# fc-comms-2.net
KiCad netlist of a schematic drawn in EAGLE
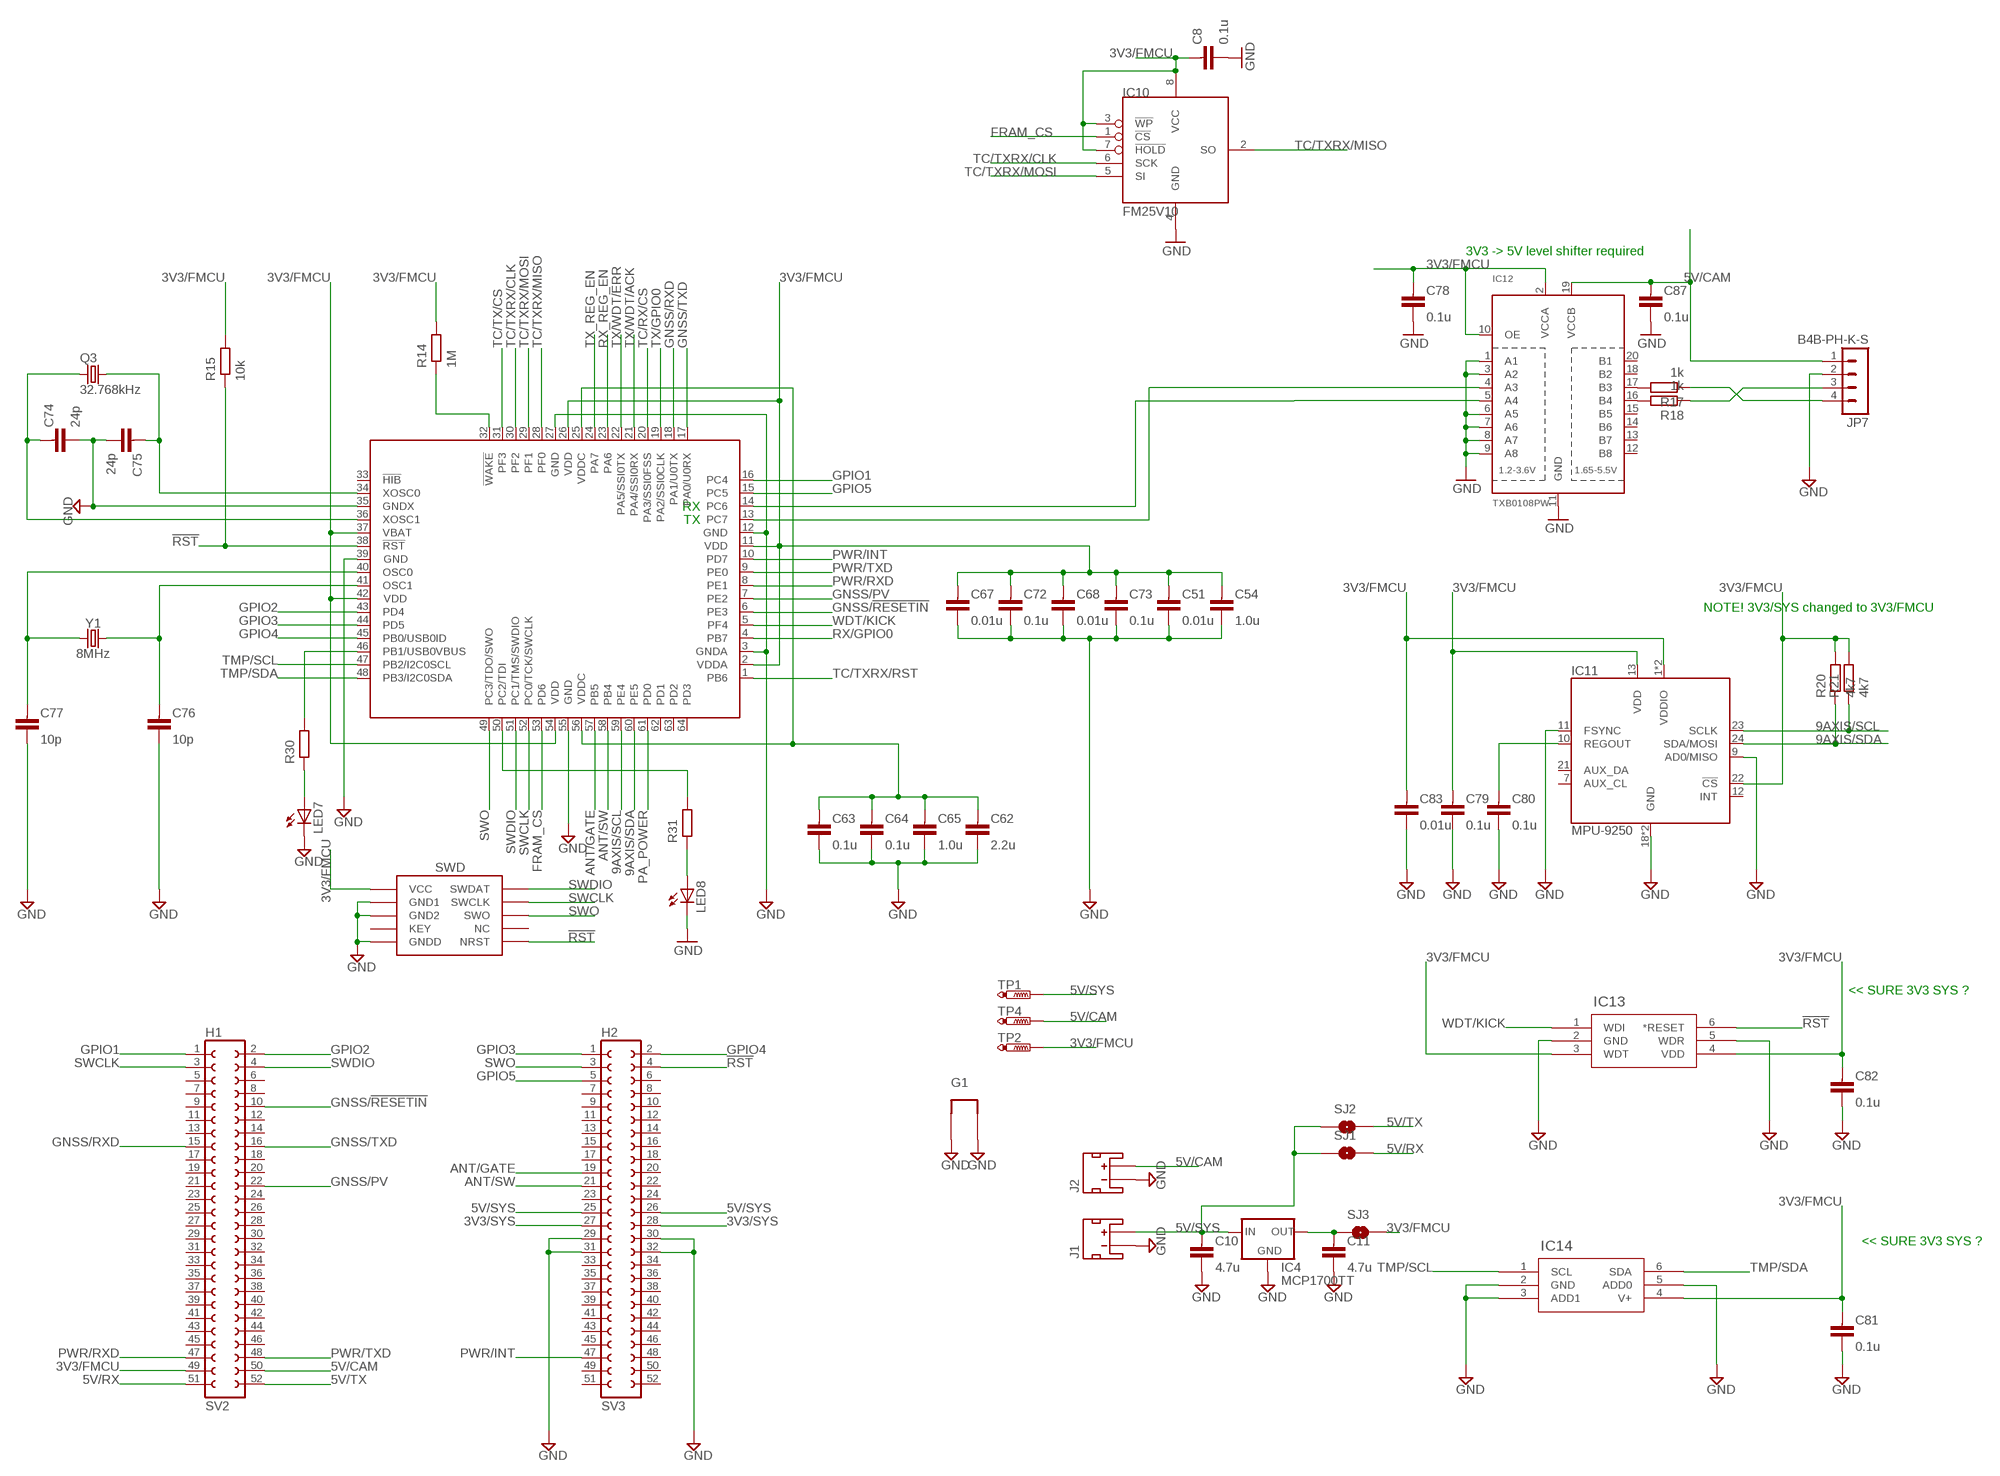
[diagram p0: schematic, sheet 1]
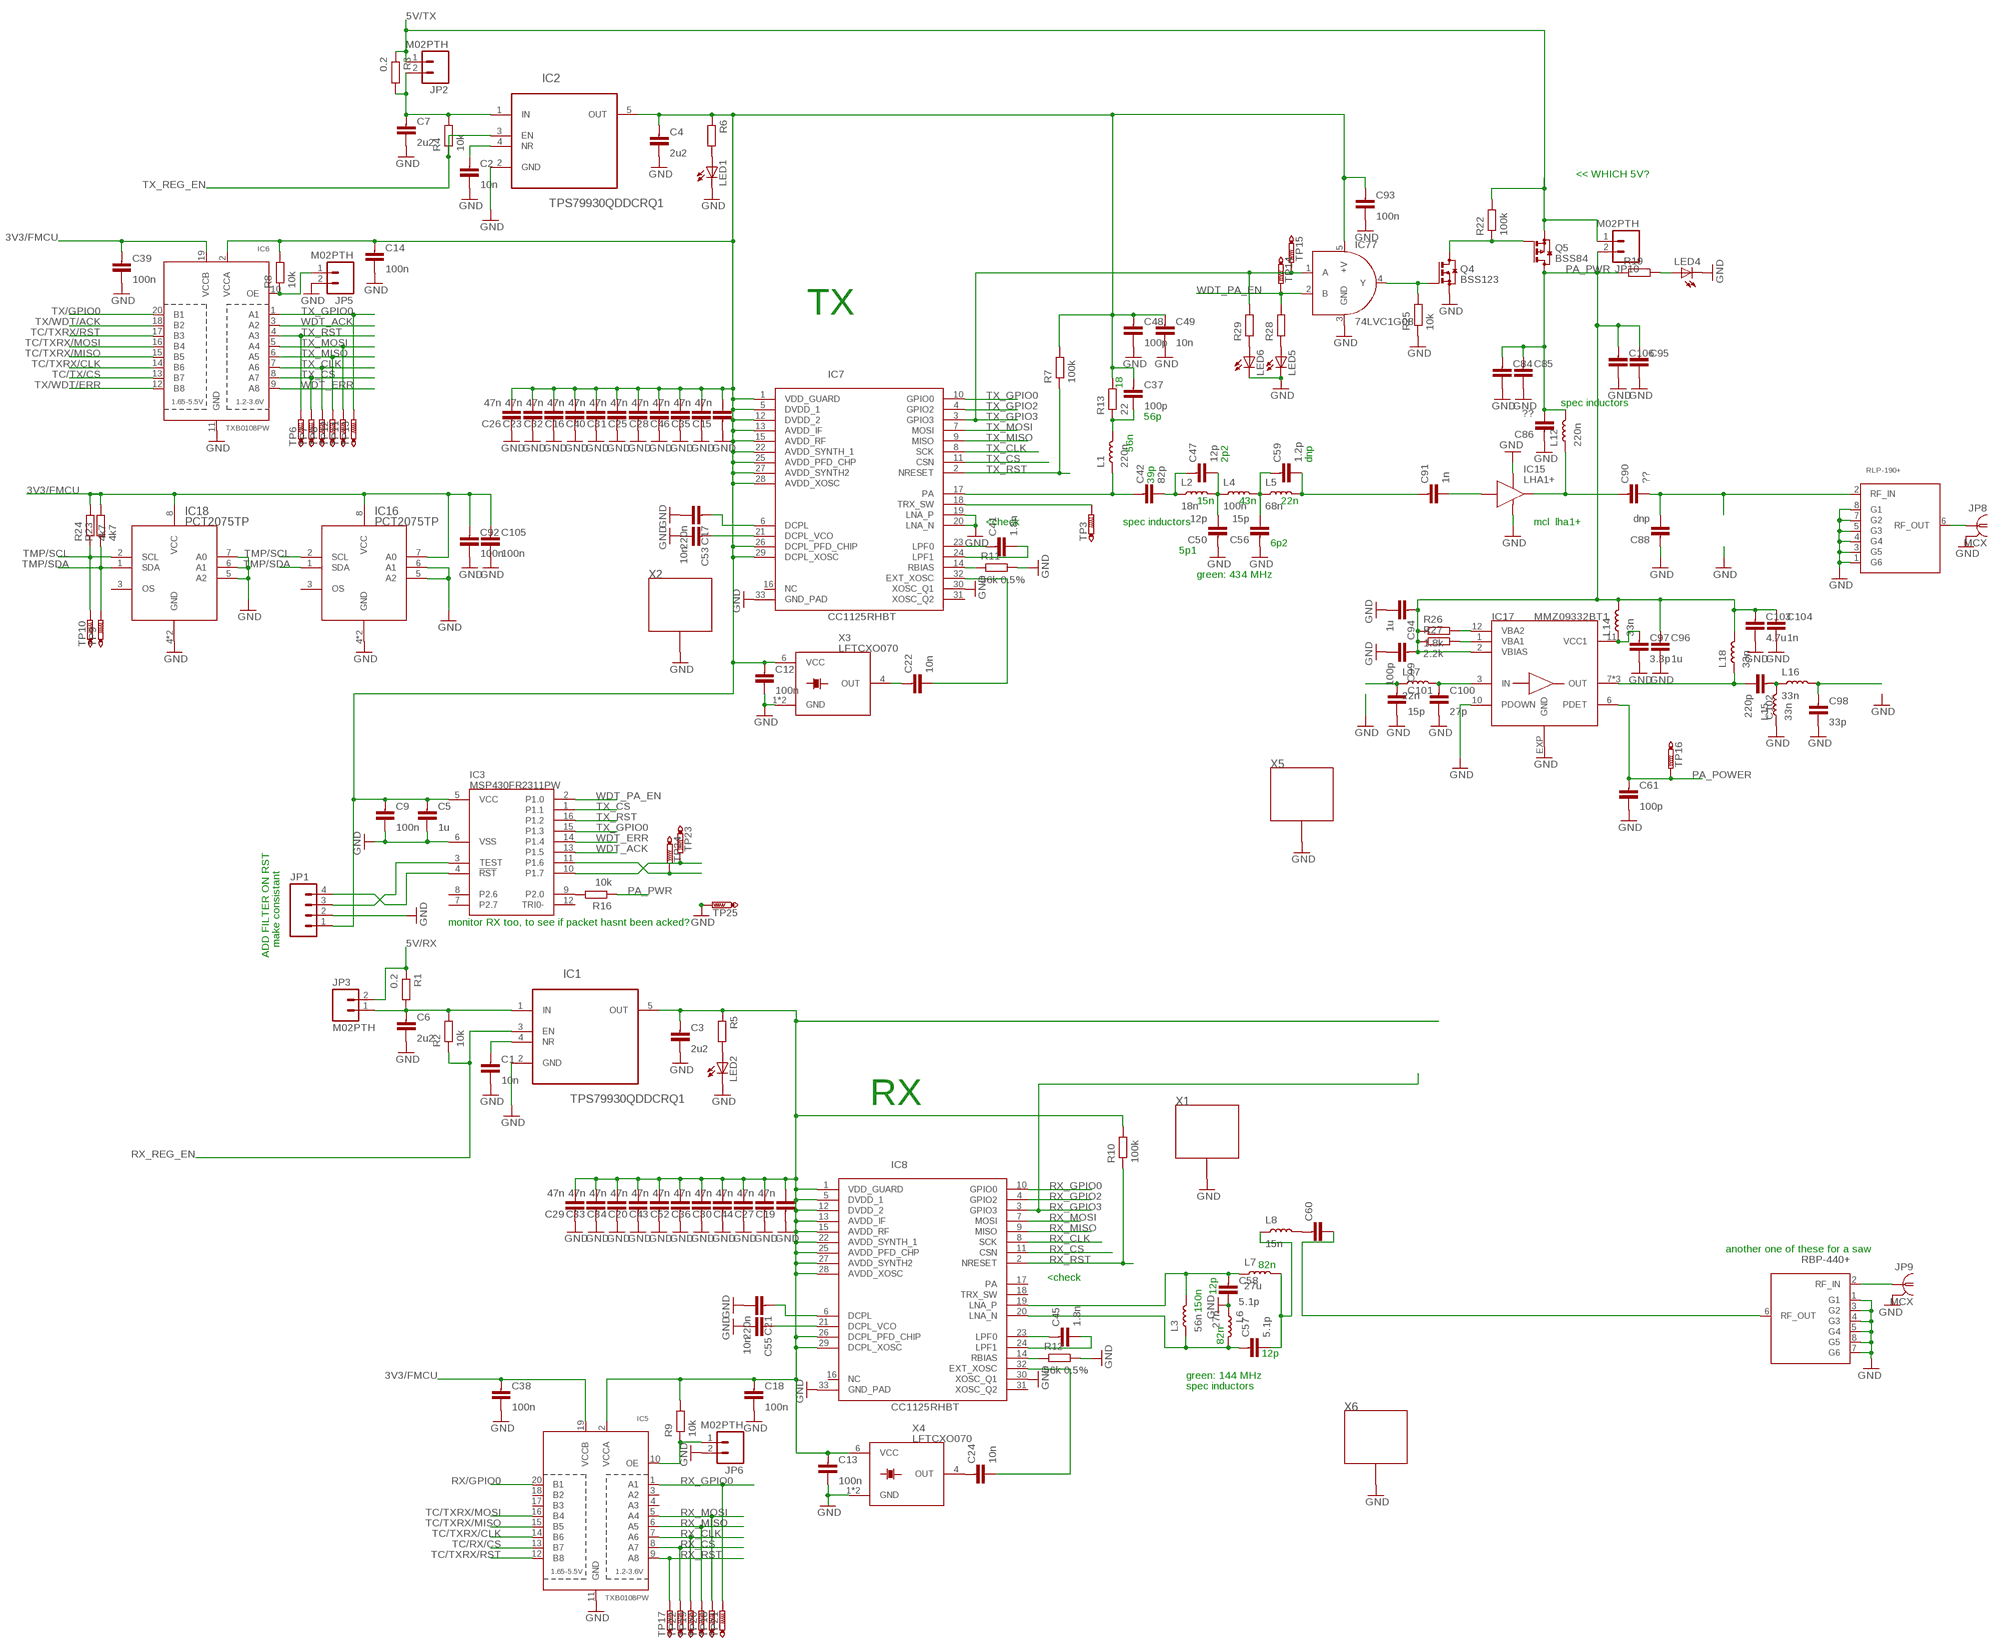
[diagram p1: schematic, sheet 2]

(export (version "E")
  (design (tool "Eeschema 10.0.6"))
  (components
    (comp (ref "C8")
      (value "0.1u")
      (footprint "eagle-import:C0603-N")
      (libsource (lib "eagle-import") (part "CAPACITOR0603-N"))
    )
    (comp (ref "C10")
      (value "4.7u")
      (footprint "eagle-import:C0603-N")
      (libsource (lib "eagle-import") (part "CAPACITOR0603-N"))
    )
    (comp (ref "C11")
      (value "4.7u")
      (footprint "eagle-import:C0603-N")
      (libsource (lib "eagle-import") (part "CAPACITOR0603-N"))
    )
    (comp (ref "C51")
      (value "0.01u")
      (footprint "eagle-import:C0603-N")
      (libsource (lib "eagle-import") (part "CAPACITOR0603-N"))
    )
    (comp (ref "C54")
      (value "1.0u")
      (footprint "eagle-import:C0603-N")
      (libsource (lib "eagle-import") (part "CAPACITOR0603-N"))
    )
    (comp (ref "C62")
      (value "2.2u")
      (footprint "eagle-import:C0603-N")
      (libsource (lib "eagle-import") (part "CAPACITOR0603-N"))
    )
    (comp (ref "C63")
      (value "0.1u")
      (footprint "eagle-import:C0603-N")
      (libsource (lib "eagle-import") (part "CAPACITOR0603-N"))
    )
    (comp (ref "C64")
      (value "0.1u")
      (footprint "eagle-import:C0603-N")
      (libsource (lib "eagle-import") (part "CAPACITOR0603-N"))
    )
    (comp (ref "C65")
      (value "1.0u")
      (footprint "eagle-import:C0603-N")
      (libsource (lib "eagle-import") (part "CAPACITOR0603-N"))
    )
    (comp (ref "C67")
      (value "0.01u")
      (footprint "eagle-import:C0603-N")
      (libsource (lib "eagle-import") (part "CAPACITOR0603-N"))
    )
    (comp (ref "C68")
      (value "0.01u")
      (footprint "eagle-import:C0603-N")
      (libsource (lib "eagle-import") (part "CAPACITOR0603-N"))
    )
    (comp (ref "C72")
      (value "0.1u")
      (footprint "eagle-import:C0603-N")
      (libsource (lib "eagle-import") (part "CAPACITOR0603-N"))
    )
    (comp (ref "C73")
      (value "0.1u")
      (footprint "eagle-import:C0603-N")
      (libsource (lib "eagle-import") (part "CAPACITOR0603-N"))
    )
    (comp (ref "C74")
      (value "24p")
      (footprint "eagle-import:C0603-N")
      (libsource (lib "eagle-import") (part "CAPACITOR0603-N"))
    )
    (comp (ref "C75")
      (value "24p")
      (footprint "eagle-import:C0603-N")
      (libsource (lib "eagle-import") (part "CAPACITOR0603-N"))
    )
    (comp (ref "C76")
      (value "10p")
      (footprint "eagle-import:C0603-N")
      (libsource (lib "eagle-import") (part "CAPACITOR0603-N"))
    )
    (comp (ref "C77")
      (value "10p")
      (footprint "eagle-import:C0603-N")
      (libsource (lib "eagle-import") (part "CAPACITOR0603-N"))
    )
    (comp (ref "C78")
      (value "0.1u")
      (footprint "eagle-import:C0603-N")
      (libsource (lib "eagle-import") (part "CAPACITOR0603-N"))
    )
    (comp (ref "C79")
      (value "0.1u")
      (footprint "eagle-import:C0603-N")
      (libsource (lib "eagle-import") (part "CAPACITOR0603-N"))
    )
    (comp (ref "C80")
      (value "0.1u")
      (footprint "eagle-import:C0603-N")
      (libsource (lib "eagle-import") (part "CAPACITOR0603-N"))
    )
    (comp (ref "C81")
      (value "0.1u")
      (footprint "eagle-import:C0603-N")
      (libsource (lib "eagle-import") (part "CAPACITOR0603-N"))
    )
    (comp (ref "C82")
      (value "0.1u")
      (footprint "eagle-import:C0603-N")
      (libsource (lib "eagle-import") (part "CAPACITOR0603-N"))
    )
    (comp (ref "C83")
      (value "0.01u")
      (footprint "eagle-import:C0603-N")
      (libsource (lib "eagle-import") (part "CAPACITOR0603-N"))
    )
    (comp (ref "C87")
      (value "0.1u")
      (footprint "eagle-import:C0603-N")
      (libsource (lib "eagle-import") (part "CAPACITOR0603-N"))
    )
    (comp (ref "G1")
      (value "GND-LOOPL")
      (footprint "eagle-import:GND-LOOP-0.4")
      (libsource (lib "eagle-import") (part "GND-LOOPL"))
    )
    (comp (ref "IC4")
      (value "MCP1700TT")
      (footprint "eagle-import:SOT23")
      (libsource (lib "eagle-import") (part "MCP1700TT"))
    )
    (comp (ref "IC9")
      (value "TM4C123[7,G]XXPM")
      (footprint "eagle-import:PM_S-PQFP-G64")
      (libsource (lib "eagle-import") (part "TM4C123[7,G]XXPM"))
    )
    (comp (ref "IC10")
      (value "FM25V10")
      (footprint "eagle-import:SO-08M")
      (libsource (lib "eagle-import") (part "FM25V10"))
    )
    (comp (ref "IC11")
      (value "MPU-9250")
      (footprint "eagle-import:QFN-24_3MM")
      (libsource (lib "eagle-import") (part "MPU-9250"))
    )
    (comp (ref "IC12")
      (value "TXB0108PW")
      (footprint "eagle-import:TSSOP20")
      (libsource (lib "eagle-import") (part "TXB0108PW"))
    )
    (comp (ref "IC13")
      (value "TPS3813K33-EP_DBV_6")
      (footprint "eagle-import:DBV6")
      (fields
        (field (name "GENERIC_PART_NUMBER") "TPS3813K33-EP")
        (field (name "MANUFACTURER") "Texas Instruments")
        (field (name "MANUFACTURER_PART_NUMBER") "tps3813k33-ep_dbv_6")
      )
      (libsource (lib "eagle-import") (part "TPS3813K33-EP_DBV_6"))
    )
    (comp (ref "IC14")
      (value "TMP100-EP_DBV_6")
      (footprint "eagle-import:DBV6")
      (fields
        (field (name "GENERIC_PART_NUMBER") "TMP100-EP")
        (field (name "MANUFACTURER") "Texas Instruments")
        (field (name "MANUFACTURER_PART_NUMBER") "tmp100-ep_dbv_6")
      )
      (libsource (lib "eagle-import") (part "TMP100-EP_DBV_6"))
    )
    (comp (ref "J1")
      (value "JST_2MM_MALE_TH")
      (footprint "eagle-import:JST-2-TH")
      (libsource (lib "eagle-import") (part "JST_2MM_MALE_TH"))
    )
    (comp (ref "J2")
      (value "JST_2MM_MALE_TH")
      (footprint "eagle-import:JST-2-TH")
      (libsource (lib "eagle-import") (part "JST_2MM_MALE_TH"))
    )
    (comp (ref "J3")
      (value "SWD_SHROUD")
      (footprint "eagle-import:SWD_PTH_SHROUD")
      (libsource (lib "eagle-import") (part "SWD_SHROUD"))
    )
    (comp (ref "JP7")
      (value "B4B-PH-K-S")
      (footprint "eagle-import:B4B-PH-K-S")
      (libsource (lib "eagle-import") (part "B4B-PH-K-S"))
    )
    (comp (ref "LED7")
      (value "LEDCHIP-LED0603")
      (footprint "eagle-import:CHIP-LED0603")
      (libsource (lib "eagle-import") (part "LEDCHIP-LED0603"))
    )
    (comp (ref "LED8")
      (value "LEDCHIP-LED0603")
      (footprint "eagle-import:CHIP-LED0603")
      (libsource (lib "eagle-import") (part "LEDCHIP-LED0603"))
    )
    (comp (ref "Q3")
      (value "32.768kHz")
      (footprint "eagle-import:RESONATOR_EPSON_FC_145")
      (libsource (lib "eagle-import") (part "RESONATOR_EPSON_FC_145"))
    )
    (comp (ref "R14")
      (value "1M")
      (footprint "eagle-import:R0603-N")
      (libsource (lib "eagle-import") (part "RESISTOR0603-N"))
    )
    (comp (ref "R15")
      (value "10k")
      (footprint "eagle-import:R0603-N")
      (libsource (lib "eagle-import") (part "RESISTOR0603-N"))
    )
    (comp (ref "R17")
      (value "1k")
      (footprint "eagle-import:R0603-N")
      (libsource (lib "eagle-import") (part "RESISTOR0603-N"))
    )
    (comp (ref "R18")
      (value "1k")
      (footprint "eagle-import:R0603-N")
      (libsource (lib "eagle-import") (part "RESISTOR0603-N"))
    )
    (comp (ref "R20")
      (value "4k7")
      (footprint "eagle-import:R0603-N")
      (libsource (lib "eagle-import") (part "RESISTOR0603-N"))
    )
    (comp (ref "R21")
      (value "4k7")
      (footprint "eagle-import:R0603-N")
      (libsource (lib "eagle-import") (part "RESISTOR0603-N"))
    )
    (comp (ref "R30")
      (value "RESISTOR0603-N")
      (footprint "eagle-import:R0603-N")
      (libsource (lib "eagle-import") (part "RESISTOR0603-N"))
    )
    (comp (ref "R31")
      (value "RESISTOR0603-N")
      (footprint "eagle-import:R0603-N")
      (libsource (lib "eagle-import") (part "RESISTOR0603-N"))
    )
    (comp (ref "SJ1")
      (value "JUMPER-PAD-2-NOYES_SILK")
      (footprint "eagle-import:PAD-JUMPER-2-NO_YES_SILK")
      (libsource (lib "eagle-import") (part "JUMPER-PAD-2-NOYES_SILK"))
    )
    (comp (ref "SJ2")
      (value "JUMPER-PAD-2-NOYES_SILK")
      (footprint "eagle-import:PAD-JUMPER-2-NO_YES_SILK")
      (libsource (lib "eagle-import") (part "JUMPER-PAD-2-NOYES_SILK"))
    )
    (comp (ref "SJ3")
      (value "JUMPER-PAD-2-NOYES_SILK")
      (footprint "eagle-import:PAD-JUMPER-2-NO_YES_SILK")
      (libsource (lib "eagle-import") (part "JUMPER-PAD-2-NOYES_SILK"))
    )
    (comp (ref "SV2")
      (value "H1")
      (footprint "eagle-import:FE26-2")
      (libsource (lib "eagle-import") (part "FE26-2"))
    )
    (comp (ref "SV3")
      (value "H2")
      (footprint "eagle-import:FE26-2")
      (libsource (lib "eagle-import") (part "FE26-2"))
    )
    (comp (ref "TP1")
      (value "PTR1PAD1-13")
      (footprint "eagle-import:P1-13")
      (libsource (lib "eagle-import") (part "PTR1PAD1-13"))
    )
    (comp (ref "TP2")
      (value "PTR1PAD1-13")
      (footprint "eagle-import:P1-13")
      (libsource (lib "eagle-import") (part "PTR1PAD1-13"))
    )
    (comp (ref "TP4")
      (value "PTR1PAD1-13")
      (footprint "eagle-import:P1-13")
      (libsource (lib "eagle-import") (part "PTR1PAD1-13"))
    )
    (comp (ref "Y1")
      (value "8MHz")
      (footprint "eagle-import:CRYSTAL-SMD-5X3.2-4PAD")
      (libsource (lib "eagle-import") (part "CRYSTAL-8MHZSMD-5X3.2"))
    )
    (comp (ref "C1")
      (value "10n")
      (footprint "eagle-import:C0603-N")
      (libsource (lib "eagle-import") (part "CAPACITOR0603-N"))
    )
    (comp (ref "C2")
      (value "10n")
      (footprint "eagle-import:C0603-N")
      (libsource (lib "eagle-import") (part "CAPACITOR0603-N"))
    )
    (comp (ref "C3")
      (value "2u2")
      (footprint "eagle-import:C0603-N")
      (libsource (lib "eagle-import") (part "CAPACITOR0603-N"))
    )
    (comp (ref "C4")
      (value "2u2")
      (footprint "eagle-import:C0603-N")
      (libsource (lib "eagle-import") (part "CAPACITOR0603-N"))
    )
    (comp (ref "C5")
      (value "1u")
      (footprint "eagle-import:C0603-N")
      (libsource (lib "eagle-import") (part "CAPACITOR0603-N"))
    )
    (comp (ref "C6")
      (value "2u2")
      (footprint "eagle-import:C0603-N")
      (libsource (lib "eagle-import") (part "CAPACITOR0603-N"))
    )
    (comp (ref "C7")
      (value "2u2")
      (footprint "eagle-import:C0603-N")
      (libsource (lib "eagle-import") (part "CAPACITOR0603-N"))
    )
    (comp (ref "C9")
      (value "100n")
      (footprint "eagle-import:C0603-N")
      (libsource (lib "eagle-import") (part "CAPACITOR0603-N"))
    )
    (comp (ref "C12")
      (value "100n")
      (footprint "eagle-import:C0603-N")
      (libsource (lib "eagle-import") (part "CAPACITOR0603-N"))
    )
    (comp (ref "C13")
      (value "100n")
      (footprint "eagle-import:C0603-N")
      (libsource (lib "eagle-import") (part "CAPACITOR0603-N"))
    )
    (comp (ref "C14")
      (value "100n")
      (footprint "eagle-import:C0603-N")
      (libsource (lib "eagle-import") (part "CAPACITOR0603-N"))
    )
    (comp (ref "C15")
      (value "47n")
      (footprint "eagle-import:C0603-N")
      (libsource (lib "eagle-import") (part "CAPACITOR0603-N"))
    )
    (comp (ref "C16")
      (value "47n")
      (footprint "eagle-import:C0603-N")
      (libsource (lib "eagle-import") (part "CAPACITOR0603-N"))
    )
    (comp (ref "C17")
      (value "220n")
      (footprint "eagle-import:C0603-N")
      (libsource (lib "eagle-import") (part "CAPACITOR0603-N"))
    )
    (comp (ref "C18")
      (value "100n")
      (footprint "eagle-import:C0603-N")
      (libsource (lib "eagle-import") (part "CAPACITOR0603-N"))
    )
    (comp (ref "C19")
      (value "47n")
      (footprint "eagle-import:C0603-N")
      (libsource (lib "eagle-import") (part "CAPACITOR0603-N"))
    )
    (comp (ref "C20")
      (value "47n")
      (footprint "eagle-import:C0603-N")
      (libsource (lib "eagle-import") (part "CAPACITOR0603-N"))
    )
    (comp (ref "C21")
      (value "220n")
      (footprint "eagle-import:C0603-N")
      (libsource (lib "eagle-import") (part "CAPACITOR0603-N"))
    )
    (comp (ref "C22")
      (value "10n")
      (footprint "eagle-import:C0603-N")
      (libsource (lib "eagle-import") (part "CAPACITOR0603-N"))
    )
    (comp (ref "C23")
      (value "47n")
      (footprint "eagle-import:C0603-N")
      (libsource (lib "eagle-import") (part "CAPACITOR0603-N"))
    )
    (comp (ref "C24")
      (value "10n")
      (footprint "eagle-import:C0603-N")
      (libsource (lib "eagle-import") (part "CAPACITOR0603-N"))
    )
    (comp (ref "C25")
      (value "47n")
      (footprint "eagle-import:C0603-N")
      (libsource (lib "eagle-import") (part "CAPACITOR0603-N"))
    )
    (comp (ref "C26")
      (value "47n")
      (footprint "eagle-import:C0603-N")
      (libsource (lib "eagle-import") (part "CAPACITOR0603-N"))
    )
    (comp (ref "C27")
      (value "47n")
      (footprint "eagle-import:C0603-N")
      (libsource (lib "eagle-import") (part "CAPACITOR0603-N"))
    )
    (comp (ref "C28")
      (value "47n")
      (footprint "eagle-import:C0603-N")
      (libsource (lib "eagle-import") (part "CAPACITOR0603-N"))
    )
    (comp (ref "C29")
      (value "47n")
      (footprint "eagle-import:C0603-N")
      (libsource (lib "eagle-import") (part "CAPACITOR0603-N"))
    )
    (comp (ref "C30")
      (value "47n")
      (footprint "eagle-import:C0603-N")
      (libsource (lib "eagle-import") (part "CAPACITOR0603-N"))
    )
    (comp (ref "C31")
      (value "47n")
      (footprint "eagle-import:C0603-N")
      (libsource (lib "eagle-import") (part "CAPACITOR0603-N"))
    )
    (comp (ref "C32")
      (value "47n")
      (footprint "eagle-import:C0603-N")
      (libsource (lib "eagle-import") (part "CAPACITOR0603-N"))
    )
    (comp (ref "C33")
      (value "47n")
      (footprint "eagle-import:C0603-N")
      (libsource (lib "eagle-import") (part "CAPACITOR0603-N"))
    )
    (comp (ref "C34")
      (value "47n")
      (footprint "eagle-import:C0603-N")
      (libsource (lib "eagle-import") (part "CAPACITOR0603-N"))
    )
    (comp (ref "C35")
      (value "47n")
      (footprint "eagle-import:C0603-N")
      (libsource (lib "eagle-import") (part "CAPACITOR0603-N"))
    )
    (comp (ref "C36")
      (value "47n")
      (footprint "eagle-import:C0603-N")
      (libsource (lib "eagle-import") (part "CAPACITOR0603-N"))
    )
    (comp (ref "C37")
      (value "100p")
      (footprint "eagle-import:C0603-N")
      (libsource (lib "eagle-import") (part "CAPACITOR0603-N"))
    )
    (comp (ref "C38")
      (value "100n")
      (footprint "eagle-import:C0603-N")
      (libsource (lib "eagle-import") (part "CAPACITOR0603-N"))
    )
    (comp (ref "C39")
      (value "100n")
      (footprint "eagle-import:C0603-N")
      (libsource (lib "eagle-import") (part "CAPACITOR0603-N"))
    )
    (comp (ref "C40")
      (value "47n")
      (footprint "eagle-import:C0603-N")
      (libsource (lib "eagle-import") (part "CAPACITOR0603-N"))
    )
    (comp (ref "C41")
      (value "1.8n")
      (footprint "eagle-import:C0603-N")
      (libsource (lib "eagle-import") (part "CAPACITOR0603-N"))
    )
    (comp (ref "C42")
      (value "82p")
      (footprint "eagle-import:C0603-N")
      (libsource (lib "eagle-import") (part "CAPACITOR0603-N"))
    )
    (comp (ref "C43")
      (value "47n")
      (footprint "eagle-import:C0603-N")
      (libsource (lib "eagle-import") (part "CAPACITOR0603-N"))
    )
    (comp (ref "C44")
      (value "47n")
      (footprint "eagle-import:C0603-N")
      (libsource (lib "eagle-import") (part "CAPACITOR0603-N"))
    )
    (comp (ref "C45")
      (value "1.8n")
      (footprint "eagle-import:C0603-N")
      (libsource (lib "eagle-import") (part "CAPACITOR0603-N"))
    )
    (comp (ref "C46")
      (value "47n")
      (footprint "eagle-import:C0603-N")
      (libsource (lib "eagle-import") (part "CAPACITOR0603-N"))
    )
    (comp (ref "C47")
      (value "12p")
      (footprint "eagle-import:C0603-N")
      (libsource (lib "eagle-import") (part "CAPACITOR0603-N"))
    )
    (comp (ref "C48")
      (value "100p")
      (footprint "eagle-import:C0603-N")
      (libsource (lib "eagle-import") (part "CAPACITOR0603-N"))
    )
    (comp (ref "C49")
      (value "10n")
      (footprint "eagle-import:C0603-N")
      (libsource (lib "eagle-import") (part "CAPACITOR0603-N"))
    )
    (comp (ref "C50")
      (value "12p")
      (footprint "eagle-import:C0603-N")
      (libsource (lib "eagle-import") (part "CAPACITOR0603-N"))
    )
    (comp (ref "C52")
      (value "47n")
      (footprint "eagle-import:C0603-N")
      (libsource (lib "eagle-import") (part "CAPACITOR0603-N"))
    )
    (comp (ref "C53")
      (value "10n")
      (footprint "eagle-import:C0603-N")
      (libsource (lib "eagle-import") (part "CAPACITOR0603-N"))
    )
    (comp (ref "C55")
      (value "10n")
      (footprint "eagle-import:C0603-N")
      (libsource (lib "eagle-import") (part "CAPACITOR0603-N"))
    )
    (comp (ref "C56")
      (value "15p")
      (footprint "eagle-import:C0603-N")
      (libsource (lib "eagle-import") (part "CAPACITOR0603-N"))
    )
    (comp (ref "C57")
      (value "5.1p")
      (footprint "eagle-import:C0603-N")
      (libsource (lib "eagle-import") (part "CAPACITOR0603-N"))
    )
    (comp (ref "C58")
      (value "5.1p")
      (footprint "eagle-import:C0603-N")
      (libsource (lib "eagle-import") (part "CAPACITOR0603-N"))
    )
    (comp (ref "C59")
      (value "1.2p")
      (footprint "eagle-import:C0603-N")
      (libsource (lib "eagle-import") (part "CAPACITOR0603-N"))
    )
    (comp (ref "C60")
      (value "CAPACITOR0603-N")
      (footprint "eagle-import:C0603-N")
      (libsource (lib "eagle-import") (part "CAPACITOR0603-N"))
    )
    (comp (ref "C61")
      (value "100p")
      (footprint "eagle-import:C0603-N")
      (libsource (lib "eagle-import") (part "CAPACITOR0603-N"))
    )
    (comp (ref "C84")
      (value "CAPACITOR0805-N")
      (footprint "eagle-import:C0805-N")
      (libsource (lib "eagle-import") (part "CAPACITOR0805-N"))
    )
    (comp (ref "C85")
      (value "CAPACITOR0805-N")
      (footprint "eagle-import:C0805-N")
      (libsource (lib "eagle-import") (part "CAPACITOR0805-N"))
    )
    (comp (ref "C86")
      (value "??")
      (footprint "eagle-import:C0603-N")
      (libsource (lib "eagle-import") (part "CAPACITOR0603-N"))
    )
    (comp (ref "C88")
      (value "dnp")
      (footprint "eagle-import:C0603-N")
      (libsource (lib "eagle-import") (part "CAPACITOR0603-N"))
    )
    (comp (ref "C90")
      (value "??")
      (footprint "eagle-import:C0603-N")
      (libsource (lib "eagle-import") (part "CAPACITOR0603-N"))
    )
    (comp (ref "C91")
      (value "1n")
      (footprint "eagle-import:C0603-N")
      (libsource (lib "eagle-import") (part "CAPACITOR0603-N"))
    )
    (comp (ref "C92")
      (value "100n")
      (footprint "eagle-import:C0603-N")
      (libsource (lib "eagle-import") (part "CAPACITOR0603-N"))
    )
    (comp (ref "C93")
      (value "100n")
      (footprint "eagle-import:C0603-N")
      (libsource (lib "eagle-import") (part "CAPACITOR0603-N"))
    )
    (comp (ref "C94")
      (value "1u")
      (footprint "eagle-import:C0603-N")
      (libsource (lib "eagle-import") (part "CAPACITOR0603-N"))
    )
    (comp (ref "C95")
      (value "CAPACITOR0805-N")
      (footprint "eagle-import:C0805-N")
      (libsource (lib "eagle-import") (part "CAPACITOR0805-N"))
    )
    (comp (ref "C96")
      (value "1u")
      (footprint "eagle-import:C0603-N")
      (libsource (lib "eagle-import") (part "CAPACITOR0603-N"))
    )
    (comp (ref "C97")
      (value "3.3p")
      (footprint "eagle-import:C0603-N")
      (libsource (lib "eagle-import") (part "CAPACITOR0603-N"))
    )
    (comp (ref "C98")
      (value "33p")
      (footprint "eagle-import:C0603-N")
      (libsource (lib "eagle-import") (part "CAPACITOR0603-N"))
    )
    (comp (ref "C99")
      (value "100p")
      (footprint "eagle-import:C0603-N")
      (libsource (lib "eagle-import") (part "CAPACITOR0603-N"))
    )
    (comp (ref "C100")
      (value "27p")
      (footprint "eagle-import:C0603-N")
      (libsource (lib "eagle-import") (part "CAPACITOR0603-N"))
    )
    (comp (ref "C101")
      (value "15p")
      (footprint "eagle-import:C0603-N")
      (libsource (lib "eagle-import") (part "CAPACITOR0603-N"))
    )
    (comp (ref "C102")
      (value "220p")
      (footprint "eagle-import:C0603-N")
      (libsource (lib "eagle-import") (part "CAPACITOR0603-N"))
    )
    (comp (ref "C103")
      (value "4.7u")
      (footprint "eagle-import:C0603-N")
      (libsource (lib "eagle-import") (part "CAPACITOR0603-N"))
    )
    (comp (ref "C104")
      (value "1n")
      (footprint "eagle-import:C0603-N")
      (libsource (lib "eagle-import") (part "CAPACITOR0603-N"))
    )
    (comp (ref "C105")
      (value "100n")
      (footprint "eagle-import:C0603-N")
      (libsource (lib "eagle-import") (part "CAPACITOR0603-N"))
    )
    (comp (ref "C106")
      (value "CAPACITOR0805-N")
      (footprint "eagle-import:C0805-N")
      (libsource (lib "eagle-import") (part "CAPACITOR0805-N"))
    )
    (comp (ref "FL2")
      (value "SAW_FILTER_CS")
      (footprint "eagle-import:PL-176")
      (libsource (lib "eagle-import") (part "SAW_FILTER_CS"))
    )
    (comp (ref "FL3")
      (value "LPF_CS")
      (footprint "eagle-import:PL-176")
      (libsource (lib "eagle-import") (part "LPF_CS"))
    )
    (comp (ref "IC1")
      (value "TPS79930QDDCRQ1")
      (footprint "eagle-import:SOT95P280X110-5N")
      (fields (field (name "MPN") "TPS79933QDDCRQ1"))
      (libsource (lib "eagle-import") (part "TPS79933QDDCRQ1"))
    )
    (comp (ref "IC2")
      (value "TPS79930QDDCRQ1")
      (footprint "eagle-import:SOT95P280X110-5N")
      (fields (field (name "MPN") "TPS79933QDDCRQ1"))
      (libsource (lib "eagle-import") (part "TPS79933QDDCRQ1"))
    )
    (comp (ref "IC3")
      (value "MSP430FR2311PW")
      (footprint "eagle-import:SSOP16")
      (libsource (lib "eagle-import") (part "MSP430FR2311PW"))
    )
    (comp (ref "IC5")
      (value "TXB0108PW")
      (footprint "eagle-import:TSSOP20")
      (libsource (lib "eagle-import") (part "TXB0108PW"))
    )
    (comp (ref "IC6")
      (value "TXB0108PW")
      (footprint "eagle-import:TSSOP20")
      (libsource (lib "eagle-import") (part "TXB0108PW"))
    )
    (comp (ref "IC7")
      (value "CC1125RHBT")
      (footprint "eagle-import:QFN32_5X5")
      (libsource (lib "eagle-import") (part "CC1125RHBT"))
    )
    (comp (ref "IC8")
      (value "CC1125RHBT")
      (footprint "eagle-import:QFN32_5X5")
      (libsource (lib "eagle-import") (part "CC1125RHBT"))
    )
    (comp (ref "IC15")
      (value "LHA1+")
      (footprint "eagle-import:PA")
      (libsource (lib "eagle-import") (part "PA"))
    )
    (comp (ref "IC16")
      (value "PCT2075TP")
      (footprint "eagle-import:HWSON8")
      (libsource (lib "eagle-import") (part "PCT2075TP"))
    )
    (comp (ref "IC17")
      (value "MMZ09332BT1")
      (footprint "eagle-import:QFN3X3-6")
      (libsource (lib "eagle-import") (part "MMZ09332BT1"))
    )
    (comp (ref "IC18")
      (value "PCT2075TP")
      (footprint "eagle-import:HWSON8")
      (libsource (lib "eagle-import") (part "PCT2075TP"))
    )
    (comp (ref "IC77")
      (value "74LVC1G08")
      (footprint "eagle-import:SOT23-5")
      (libsource (lib "eagle-import") (part "SN74LVC1G08"))
    )
    (comp (ref "JP1")
      (value "M04PTH")
      (footprint "eagle-import:1X04")
      (libsource (lib "eagle-import") (part "M04PTH"))
    )
    (comp (ref "JP2")
      (value "M02PTH")
      (footprint "eagle-import:1X02")
      (libsource (lib "eagle-import") (part "M02PTH"))
    )
    (comp (ref "JP3")
      (value "M02PTH")
      (footprint "eagle-import:1X02")
      (libsource (lib "eagle-import") (part "M02PTH"))
    )
    (comp (ref "JP5")
      (value "M02PTH")
      (footprint "eagle-import:1X02")
      (libsource (lib "eagle-import") (part "M02PTH"))
    )
    (comp (ref "JP6")
      (value "M02PTH")
      (footprint "eagle-import:1X02")
      (libsource (lib "eagle-import") (part "M02PTH"))
    )
    (comp (ref "JP8")
      (value "MCX")
      (footprint "eagle-import:MCX-STRAIGHT")
      (libsource (lib "eagle-import") (part "MCX"))
    )
    (comp (ref "JP9")
      (value "MCX")
      (footprint "eagle-import:MCX-STRAIGHT")
      (libsource (lib "eagle-import") (part "MCX"))
    )
    (comp (ref "JP10")
      (value "M02PTH")
      (footprint "eagle-import:1X02")
      (libsource (lib "eagle-import") (part "M02PTH"))
    )
    (comp (ref "L1")
      (value "220n")
      (footprint "eagle-import:L0603-N")
      (libsource (lib "eagle-import") (part "INDUCTOR0603-N"))
    )
    (comp (ref "L2")
      (value "18n")
      (footprint "eagle-import:L0603-N")
      (libsource (lib "eagle-import") (part "INDUCTOR0603-N"))
    )
    (comp (ref "L3")
      (value "56n")
      (footprint "eagle-import:L0603-N")
      (libsource (lib "eagle-import") (part "INDUCTOR0603-N"))
    )
    (comp (ref "L4")
      (value "100n")
      (footprint "eagle-import:L0603-N")
      (libsource (lib "eagle-import") (part "INDUCTOR0603-N"))
    )
    (comp (ref "L5")
      (value "68n")
      (footprint "eagle-import:L0603-N")
      (libsource (lib "eagle-import") (part "INDUCTOR0603-N"))
    )
    (comp (ref "L6")
      (value "27n")
      (footprint "eagle-import:L0603-N")
      (libsource (lib "eagle-import") (part "INDUCTOR0603-N"))
    )
    (comp (ref "L7")
      (value "27u")
      (footprint "eagle-import:L0603-N")
      (libsource (lib "eagle-import") (part "INDUCTOR0603-N"))
    )
    (comp (ref "L8")
      (value "15n")
      (footprint "eagle-import:L0603-N")
      (libsource (lib "eagle-import") (part "INDUCTOR0603-N"))
    )
    (comp (ref "L12")
      (value "220n")
      (footprint "eagle-import:L0603-N")
      (libsource (lib "eagle-import") (part "INDUCTOR0603-N"))
    )
    (comp (ref "L14")
      (value "33n")
      (footprint "eagle-import:L0603-N")
      (libsource (lib "eagle-import") (part "INDUCTOR0603-N"))
    )
    (comp (ref "L15")
      (value "33n")
      (footprint "eagle-import:L0603-N")
      (libsource (lib "eagle-import") (part "INDUCTOR0603-N"))
    )
    (comp (ref "L16")
      (value "33n")
      (footprint "eagle-import:L0603-N")
      (libsource (lib "eagle-import") (part "INDUCTOR0603-N"))
    )
    (comp (ref "L17")
      (value "22n")
      (footprint "eagle-import:L0603-N")
      (libsource (lib "eagle-import") (part "INDUCTOR0603-N"))
    )
    (comp (ref "L18")
      (value "33n")
      (footprint "eagle-import:L0603-N")
      (libsource (lib "eagle-import") (part "INDUCTOR0603-N"))
    )
    (comp (ref "LED1")
      (value "LEDCHIP-LED0603")
      (footprint "eagle-import:CHIP-LED0603")
      (libsource (lib "eagle-import") (part "LEDCHIP-LED0603"))
    )
    (comp (ref "LED2")
      (value "LEDCHIP-LED0603")
      (footprint "eagle-import:CHIP-LED0603")
      (libsource (lib "eagle-import") (part "LEDCHIP-LED0603"))
    )
    (comp (ref "LED4")
      (value "LEDCHIP-LED0603")
      (footprint "eagle-import:CHIP-LED0603")
      (libsource (lib "eagle-import") (part "LEDCHIP-LED0603"))
    )
    (comp (ref "LED5")
      (value "LEDCHIP-LED0603")
      (footprint "eagle-import:CHIP-LED0603")
      (libsource (lib "eagle-import") (part "LEDCHIP-LED0603"))
    )
    (comp (ref "LED6")
      (value "LEDCHIP-LED0603")
      (footprint "eagle-import:CHIP-LED0603")
      (libsource (lib "eagle-import") (part "LEDCHIP-LED0603"))
    )
    (comp (ref "Q4")
      (value "BSS123")
      (footprint "eagle-import:SOT23")
      (libsource (lib "eagle-import") (part "BSS123"))
    )
    (comp (ref "Q5")
      (value "BSS84")
      (footprint "eagle-import:SOT23")
      (libsource (lib "eagle-import") (part "BSS84"))
    )
    (comp (ref "R1")
      (value "0.2")
      (footprint "eagle-import:R0603-N")
      (libsource (lib "eagle-import") (part "RESISTOR0603-N"))
    )
    (comp (ref "R2")
      (value "10k")
      (footprint "eagle-import:R0603-N")
      (libsource (lib "eagle-import") (part "RESISTOR0603-N"))
    )
    (comp (ref "R3")
      (value "0.2")
      (footprint "eagle-import:R0603-N")
      (libsource (lib "eagle-import") (part "RESISTOR0603-N"))
    )
    (comp (ref "R4")
      (value "10k")
      (footprint "eagle-import:R0603-N")
      (libsource (lib "eagle-import") (part "RESISTOR0603-N"))
    )
    (comp (ref "R5")
      (value "RESISTOR0603-N")
      (footprint "eagle-import:R0603-N")
      (libsource (lib "eagle-import") (part "RESISTOR0603-N"))
    )
    (comp (ref "R6")
      (value "RESISTOR0603-N")
      (footprint "eagle-import:R0603-N")
      (libsource (lib "eagle-import") (part "RESISTOR0603-N"))
    )
    (comp (ref "R7")
      (value "100k")
      (footprint "eagle-import:R0603-N")
      (libsource (lib "eagle-import") (part "RESISTOR0603-N"))
    )
    (comp (ref "R8")
      (value "10k")
      (footprint "eagle-import:R0603-N")
      (libsource (lib "eagle-import") (part "RESISTOR0603-N"))
    )
    (comp (ref "R9")
      (value "10k")
      (footprint "eagle-import:R0603-N")
      (libsource (lib "eagle-import") (part "RESISTOR0603-N"))
    )
    (comp (ref "R10")
      (value "100k")
      (footprint "eagle-import:R0603-N")
      (libsource (lib "eagle-import") (part "RESISTOR0603-N"))
    )
    (comp (ref "R11")
      (value "56k 0.5%")
      (footprint "eagle-import:R0603-N")
      (libsource (lib "eagle-import") (part "RESISTOR0603-N"))
    )
    (comp (ref "R12")
      (value "56k 0.5%")
      (footprint "eagle-import:R0603-N")
      (libsource (lib "eagle-import") (part "RESISTOR0603-N"))
    )
    (comp (ref "R13")
      (value "22")
      (footprint "eagle-import:R0603-N")
      (libsource (lib "eagle-import") (part "RESISTOR0603-N"))
    )
    (comp (ref "R16")
      (value "10k")
      (footprint "eagle-import:R0603-N")
      (libsource (lib "eagle-import") (part "RESISTOR0603-N"))
    )
    (comp (ref "R19")
      (value "RESISTOR0603-N")
      (footprint "eagle-import:R0603-N")
      (libsource (lib "eagle-import") (part "RESISTOR0603-N"))
    )
    (comp (ref "R22")
      (value "100k")
      (footprint "eagle-import:R0603-N")
      (libsource (lib "eagle-import") (part "RESISTOR0603-N"))
    )
    (comp (ref "R23")
      (value "4k7")
      (footprint "eagle-import:R0603-N")
      (libsource (lib "eagle-import") (part "RESISTOR0603-N"))
    )
    (comp (ref "R24")
      (value "4k7")
      (footprint "eagle-import:R0603-N")
      (libsource (lib "eagle-import") (part "RESISTOR0603-N"))
    )
    (comp (ref "R25")
      (value "10k")
      (footprint "eagle-import:R0603-N")
      (libsource (lib "eagle-import") (part "RESISTOR0603-N"))
    )
    (comp (ref "R26")
      (value "1.8k")
      (footprint "eagle-import:R0603-N")
      (libsource (lib "eagle-import") (part "RESISTOR0603-N"))
    )
    (comp (ref "R27")
      (value "2.2k")
      (footprint "eagle-import:R0603-N")
      (libsource (lib "eagle-import") (part "RESISTOR0603-N"))
    )
    (comp (ref "R28")
      (value "RESISTOR0603-N")
      (footprint "eagle-import:R0603-N")
      (libsource (lib "eagle-import") (part "RESISTOR0603-N"))
    )
    (comp (ref "R29")
      (value "RESISTOR0603-N")
      (footprint "eagle-import:R0603-N")
      (libsource (lib "eagle-import") (part "RESISTOR0603-N"))
    )
    (comp (ref "TP3")
      (value "PTR1B1,27")
      (footprint "eagle-import:B1,27")
      (libsource (lib "eagle-import") (part "PTR1B1,27"))
    )
    (comp (ref "TP6")
      (value "PTR1B1,27")
      (footprint "eagle-import:B1,27")
      (libsource (lib "eagle-import") (part "PTR1B1,27"))
    )
    (comp (ref "TP7")
      (value "PTR1B1,27")
      (footprint "eagle-import:B1,27")
      (libsource (lib "eagle-import") (part "PTR1B1,27"))
    )
    (comp (ref "TP8")
      (value "PTR1B1,27")
      (footprint "eagle-import:B1,27")
      (libsource (lib "eagle-import") (part "PTR1B1,27"))
    )
    (comp (ref "TP9")
      (value "PTR1B1,27")
      (footprint "eagle-import:B1,27")
      (libsource (lib "eagle-import") (part "PTR1B1,27"))
    )
    (comp (ref "TP10")
      (value "PTR1B1,27")
      (footprint "eagle-import:B1,27")
      (libsource (lib "eagle-import") (part "PTR1B1,27"))
    )
    (comp (ref "TP11")
      (value "PTR1B1,27")
      (footprint "eagle-import:B1,27")
      (libsource (lib "eagle-import") (part "PTR1B1,27"))
    )
    (comp (ref "TP12")
      (value "PTR1B1,27")
      (footprint "eagle-import:B1,27")
      (libsource (lib "eagle-import") (part "PTR1B1,27"))
    )
    (comp (ref "TP13")
      (value "PTR1B1,27")
      (footprint "eagle-import:B1,27")
      (libsource (lib "eagle-import") (part "PTR1B1,27"))
    )
    (comp (ref "TP14")
      (value "PTR1B1,27")
      (footprint "eagle-import:B1,27")
      (libsource (lib "eagle-import") (part "PTR1B1,27"))
    )
    (comp (ref "TP15")
      (value "PTR1B1,27")
      (footprint "eagle-import:B1,27")
      (libsource (lib "eagle-import") (part "PTR1B1,27"))
    )
    (comp (ref "TP16")
      (value "PTR1B1,27")
      (footprint "eagle-import:B1,27")
      (libsource (lib "eagle-import") (part "PTR1B1,27"))
    )
    (comp (ref "TP17")
      (value "PTR1B1,27")
      (footprint "eagle-import:B1,27")
      (libsource (lib "eagle-import") (part "PTR1B1,27"))
    )
    (comp (ref "TP18")
      (value "PTR1B1,27")
      (footprint "eagle-import:B1,27")
      (libsource (lib "eagle-import") (part "PTR1B1,27"))
    )
    (comp (ref "TP19")
      (value "PTR1B1,27")
      (footprint "eagle-import:B1,27")
      (libsource (lib "eagle-import") (part "PTR1B1,27"))
    )
    (comp (ref "TP20")
      (value "PTR1B1,27")
      (footprint "eagle-import:B1,27")
      (libsource (lib "eagle-import") (part "PTR1B1,27"))
    )
    (comp (ref "TP21")
      (value "PTR1B1,27")
      (footprint "eagle-import:B1,27")
      (libsource (lib "eagle-import") (part "PTR1B1,27"))
    )
    (comp (ref "TP22")
      (value "PTR1B1,27")
      (footprint "eagle-import:B1,27")
      (libsource (lib "eagle-import") (part "PTR1B1,27"))
    )
    (comp (ref "TP23")
      (value "PTR1B1,27")
      (footprint "eagle-import:B1,27")
      (libsource (lib "eagle-import") (part "PTR1B1,27"))
    )
    (comp (ref "TP24")
      (value "PTR1B1,27")
      (footprint "eagle-import:B1,27")
      (libsource (lib "eagle-import") (part "PTR1B1,27"))
    )
    (comp (ref "TP25")
      (value "PTR1B1,27")
      (footprint "eagle-import:B1,27")
      (libsource (lib "eagle-import") (part "PTR1B1,27"))
    )
    (comp (ref "X1")
      (value "SHIELD-26X26")
      (footprint "eagle-import:SHIELD-26X26")
      (libsource (lib "eagle-import") (part "SHIELD-26X26"))
    )
    (comp (ref "X2")
      (value "SHIELD-26X26")
      (footprint "eagle-import:SHIELD-26X26")
      (libsource (lib "eagle-import") (part "SHIELD-26X26"))
    )
    (comp (ref "X3")
      (value "LFTCXO070")
      (footprint "eagle-import:260-SERIES")
      (libsource (lib "eagle-import") (part "LFTCXO070"))
    )
    (comp (ref "X4")
      (value "LFTCXO070")
      (footprint "eagle-import:260-SERIES")
      (libsource (lib "eagle-import") (part "LFTCXO070"))
    )
    (comp (ref "X5")
      (value "SHIELD-26X26")
      (footprint "eagle-import:SHIELD-26X26")
      (libsource (lib "eagle-import") (part "SHIELD-26X26"))
    )
    (comp (ref "X6")
      (value "SHIELD-26X26")
      (footprint "eagle-import:SHIELD-26X26")
      (libsource (lib "eagle-import") (part "SHIELD-26X26"))
    )
  )
  (nets
    (net (code "1") (name "3V3{slash}FMCU") (class "Default")
      (node (ref "C105") (pin "1") (pinfunction "1_1") (pintype "passive"))
      (node (ref "C38") (pin "1") (pinfunction "1_1") (pintype "passive"))
      (node (ref "C39") (pin "1") (pinfunction "1_1") (pintype "passive"))
      (node (ref "C51") (pin "1") (pinfunction "1_1") (pintype "passive"))
      (node (ref "C54") (pin "1") (pinfunction "1_1") (pintype "passive"))
      (node (ref "C67") (pin "1") (pinfunction "1_1") (pintype "passive"))
      (node (ref "C68") (pin "1") (pinfunction "1_1") (pintype "passive"))
      (node (ref "C72") (pin "1") (pinfunction "1_1") (pintype "passive"))
      (node (ref "C73") (pin "1") (pinfunction "1_1") (pintype "passive"))
      (node (ref "C78") (pin "1") (pinfunction "1_1") (pintype "passive"))
      (node (ref "C79") (pin "1") (pinfunction "1_1") (pintype "passive"))
      (node (ref "C8") (pin "1") (pinfunction "1_1") (pintype "passive"))
      (node (ref "C81") (pin "1") (pinfunction "1_1") (pintype "passive"))
      (node (ref "C82") (pin "1") (pinfunction "1_1") (pintype "passive"))
      (node (ref "C83") (pin "1") (pinfunction "1_1") (pintype "passive"))
      (node (ref "C92") (pin "1") (pinfunction "1_1") (pintype "passive"))
      (node (ref "IC10") (pin "3") (pinfunction "~{WP}_3") (pintype "input"))
      (node (ref "IC10") (pin "7") (pinfunction "~{HOLD}_7") (pintype "input"))
      (node (ref "IC10") (pin "8") (pinfunction "VCC_8") (pintype "power_in"))
      (node (ref "IC11") (pin "1") (pinfunction "VDDIO_1") (pintype "bidirectional"))
      (node (ref "IC11") (pin "13") (pinfunction "VDD_13") (pintype "bidirectional"))
      (node (ref "IC11") (pin "22") (pinfunction "~{CS}_22") (pintype "bidirectional"))
      (node (ref "IC11") (pin "8") (pinfunction "VDDIO_8") (pintype "bidirectional"))
      (node (ref "IC12") (pin "10") (pinfunction "OE_10") (pintype "bidirectional"))
      (node (ref "IC12") (pin "2") (pinfunction "VCCA_2") (pintype "bidirectional"))
      (node (ref "IC13") (pin "3") (pinfunction "WDT_3") (pintype "input"))
      (node (ref "IC13") (pin "4") (pinfunction "VDD_4") (pintype "input"))
      (node (ref "IC14") (pin "4") (pinfunction "V+_4") (pintype "power_in"))
      (node (ref "IC16") (pin "7") (pinfunction "A0_7") (pintype "input"))
      (node (ref "IC16") (pin "8") (pinfunction "VCC_8") (pintype "power_in"))
      (node (ref "IC18") (pin "8") (pinfunction "VCC_8") (pintype "power_in"))
      (node (ref "IC5") (pin "19") (pinfunction "VCCB_19") (pintype "bidirectional"))
      (node (ref "IC6") (pin "19") (pinfunction "VCCB_19") (pintype "bidirectional"))
      (node (ref "IC9") (pin "11") (pinfunction "VDD_11") (pintype "bidirectional"))
      (node (ref "IC9") (pin "2") (pinfunction "VDDA_2") (pintype "bidirectional"))
      (node (ref "IC9") (pin "26") (pinfunction "VDD_26") (pintype "bidirectional"))
      (node (ref "IC9") (pin "37") (pinfunction "VBAT_37") (pintype "bidirectional"))
      (node (ref "IC9") (pin "42") (pinfunction "VDD_42") (pintype "bidirectional"))
      (node (ref "IC9") (pin "54") (pinfunction "VDD_54") (pintype "bidirectional"))
      (node (ref "J3") (pin "1") (pinfunction "VCC_1") (pintype "power_in"))
      (node (ref "R14") (pin "2") (pinfunction "P$2_2") (pintype "passive"))
      (node (ref "R15") (pin "2") (pinfunction "P$2_2") (pintype "passive"))
      (node (ref "R20") (pin "2") (pinfunction "P$2_2") (pintype "passive"))
      (node (ref "R21") (pin "2") (pinfunction "P$2_2") (pintype "passive"))
      (node (ref "R23") (pin "2") (pinfunction "P$2_2") (pintype "passive"))
      (node (ref "R24") (pin "2") (pinfunction "P$2_2") (pintype "passive"))
      (node (ref "SJ3") (pin "2") (pinfunction "2_2") (pintype "passive"))
      (node (ref "SV2") (pin "49") (pinfunction "49_49") (pintype "passive"))
      (node (ref "TP2") (pin "TP") (pinfunction "TP_TP") (pintype "input"))
    )
    (net (code "2") (name "3V3{slash}SYS") (class "Default")
      (node (ref "SV3") (pin "27") (pinfunction "27_27") (pintype "passive"))
      (node (ref "SV3") (pin "28") (pinfunction "28_28") (pintype "passive"))
    )
    (net (code "3") (name "5V{slash}CAM") (class "Default")
      (node (ref "C87") (pin "1") (pinfunction "1_1") (pintype "passive"))
      (node (ref "IC12") (pin "19") (pinfunction "VCCB_19") (pintype "bidirectional"))
      (node (ref "J2") (pin "1") (pinfunction "+_1") (pintype "bidirectional"))
      (node (ref "JP7") (pin "1") (pinfunction "1_1") (pintype "passive"))
      (node (ref "SV2") (pin "50") (pinfunction "50_50") (pintype "passive"))
      (node (ref "TP4") (pin "TP") (pinfunction "TP_TP") (pintype "input"))
    )
    (net (code "4") (name "5V{slash}RX") (class "Default")
      (node (ref "JP3") (pin "2") (pinfunction "2_2") (pintype "passive"))
      (node (ref "R1") (pin "1") (pinfunction "P$1_1") (pintype "passive"))
      (node (ref "SJ1") (pin "2") (pinfunction "2_2") (pintype "passive"))
      (node (ref "SV2") (pin "51") (pinfunction "51_51") (pintype "passive"))
    )
    (net (code "5") (name "5V{slash}SYS") (class "Default")
      (node (ref "C10") (pin "1") (pinfunction "1_1") (pintype "passive"))
      (node (ref "IC4") (pin "3") (pinfunction "IN_3") (pintype "input"))
      (node (ref "J1") (pin "1") (pinfunction "+_1") (pintype "bidirectional"))
      (node (ref "SJ1") (pin "1") (pinfunction "1_1") (pintype "passive"))
      (node (ref "SJ2") (pin "1") (pinfunction "1_1") (pintype "passive"))
      (node (ref "SV3") (pin "25") (pinfunction "25_25") (pintype "passive"))
      (node (ref "SV3") (pin "26") (pinfunction "26_26") (pintype "passive"))
      (node (ref "TP1") (pin "TP") (pinfunction "TP_TP") (pintype "input"))
    )
    (net (code "6") (name "5V{slash}TX") (class "Default")
      (node (ref "JP10") (pin "1") (pinfunction "1_1") (pintype "passive"))
      (node (ref "JP2") (pin "1") (pinfunction "1_1") (pintype "passive"))
      (node (ref "Q5") (pin "2") (pinfunction "S_2") (pintype "passive"))
      (node (ref "R22") (pin "2") (pinfunction "P$2_2") (pintype "passive"))
      (node (ref "R3") (pin "1") (pinfunction "P$1_1") (pintype "passive"))
      (node (ref "SJ2") (pin "2") (pinfunction "2_2") (pintype "passive"))
      (node (ref "SV2") (pin "52") (pinfunction "52_52") (pintype "passive"))
    )
    (net (code "7") (name "9AXIS{slash}SCL") (class "Default")
      (node (ref "IC11") (pin "23") (pinfunction "SCLK_23") (pintype "bidirectional"))
      (node (ref "IC9") (pin "59") (pinfunction "PE4_59") (pintype "bidirectional"))
      (node (ref "R21") (pin "1") (pinfunction "P$1_1") (pintype "passive"))
    )
    (net (code "8") (name "9AXIS{slash}SDA") (class "Default")
      (node (ref "IC11") (pin "24") (pinfunction "SDA/MOSI_24") (pintype "bidirectional"))
      (node (ref "IC9") (pin "60") (pinfunction "PE5_60") (pintype "bidirectional"))
      (node (ref "R20") (pin "1") (pinfunction "P$1_1") (pintype "passive"))
    )
    (net (code "9") (name "ANT{slash}GATE") (class "Default")
      (node (ref "IC9") (pin "57") (pinfunction "PB5_57") (pintype "bidirectional"))
      (node (ref "SV3") (pin "19") (pinfunction "19_19") (pintype "passive"))
    )
    (net (code "10") (name "ANT{slash}SW") (class "Default")
      (node (ref "IC9") (pin "58") (pinfunction "PB4_58") (pintype "bidirectional"))
      (node (ref "SV3") (pin "21") (pinfunction "21_21") (pintype "passive"))
    )
    (net (code "11") (name "FRAM_CS") (class "Default")
      (node (ref "IC10") (pin "1") (pinfunction "~{CS}_1") (pintype "input"))
      (node (ref "IC9") (pin "53") (pinfunction "PD6_53") (pintype "bidirectional"))
    )
    (net (code "12") (name "GND") (class "Default")
      (node (ref "C1") (pin "2") (pinfunction "2_2") (pintype "passive"))
      (node (ref "C10") (pin "2") (pinfunction "2_2") (pintype "passive"))
      (node (ref "C100") (pin "2") (pinfunction "2_2") (pintype "passive"))
      (node (ref "C101") (pin "2") (pinfunction "2_2") (pintype "passive"))
      (node (ref "C103") (pin "2") (pinfunction "2_2") (pintype "passive"))
      (node (ref "C104") (pin "2") (pinfunction "2_2") (pintype "passive"))
      (node (ref "C105") (pin "2") (pinfunction "2_2") (pintype "passive"))
      (node (ref "C106") (pin "2") (pinfunction "2_2") (pintype "passive"))
      (node (ref "C11") (pin "2") (pinfunction "2_2") (pintype "passive"))
      (node (ref "C12") (pin "2") (pinfunction "2_2") (pintype "passive"))
      (node (ref "C13") (pin "2") (pinfunction "2_2") (pintype "passive"))
      (node (ref "C14") (pin "2") (pinfunction "2_2") (pintype "passive"))
      (node (ref "C15") (pin "1") (pinfunction "1_1") (pintype "passive"))
      (node (ref "C16") (pin "1") (pinfunction "1_1") (pintype "passive"))
      (node (ref "C17") (pin "2") (pinfunction "2_2") (pintype "passive"))
      (node (ref "C18") (pin "2") (pinfunction "2_2") (pintype "passive"))
      (node (ref "C19") (pin "1") (pinfunction "1_1") (pintype "passive"))
      (node (ref "C2") (pin "2") (pinfunction "2_2") (pintype "passive"))
      (node (ref "C20") (pin "1") (pinfunction "1_1") (pintype "passive"))
      (node (ref "C21") (pin "2") (pinfunction "2_2") (pintype "passive"))
      (node (ref "C23") (pin "1") (pinfunction "1_1") (pintype "passive"))
      (node (ref "C25") (pin "1") (pinfunction "1_1") (pintype "passive"))
      (node (ref "C26") (pin "1") (pinfunction "1_1") (pintype "passive"))
      (node (ref "C27") (pin "1") (pinfunction "1_1") (pintype "passive"))
      (node (ref "C28") (pin "1") (pinfunction "1_1") (pintype "passive"))
      (node (ref "C29") (pin "1") (pinfunction "1_1") (pintype "passive"))
      (node (ref "C3") (pin "2") (pinfunction "2_2") (pintype "passive"))
      (node (ref "C30") (pin "1") (pinfunction "1_1") (pintype "passive"))
      (node (ref "C31") (pin "1") (pinfunction "1_1") (pintype "passive"))
      (node (ref "C32") (pin "1") (pinfunction "1_1") (pintype "passive"))
      (node (ref "C33") (pin "1") (pinfunction "1_1") (pintype "passive"))
      (node (ref "C34") (pin "1") (pinfunction "1_1") (pintype "passive"))
      (node (ref "C35") (pin "1") (pinfunction "1_1") (pintype "passive"))
      (node (ref "C36") (pin "1") (pinfunction "1_1") (pintype "passive"))
      (node (ref "C38") (pin "2") (pinfunction "2_2") (pintype "passive"))
      (node (ref "C39") (pin "2") (pinfunction "2_2") (pintype "passive"))
      (node (ref "C4") (pin "2") (pinfunction "2_2") (pintype "passive"))
      (node (ref "C40") (pin "1") (pinfunction "1_1") (pintype "passive"))
      (node (ref "C43") (pin "1") (pinfunction "1_1") (pintype "passive"))
      (node (ref "C44") (pin "1") (pinfunction "1_1") (pintype "passive"))
      (node (ref "C46") (pin "1") (pinfunction "1_1") (pintype "passive"))
      (node (ref "C48") (pin "2") (pinfunction "2_2") (pintype "passive"))
      (node (ref "C49") (pin "2") (pinfunction "2_2") (pintype "passive"))
      (node (ref "C5") (pin "2") (pinfunction "2_2") (pintype "passive"))
      (node (ref "C50") (pin "1") (pinfunction "1_1") (pintype "passive"))
      (node (ref "C51") (pin "2") (pinfunction "2_2") (pintype "passive"))
      (node (ref "C52") (pin "1") (pinfunction "1_1") (pintype "passive"))
      (node (ref "C53") (pin "2") (pinfunction "2_2") (pintype "passive"))
      (node (ref "C54") (pin "2") (pinfunction "2_2") (pintype "passive"))
      (node (ref "C55") (pin "2") (pinfunction "2_2") (pintype "passive"))
      (node (ref "C56") (pin "1") (pinfunction "1_1") (pintype "passive"))
      (node (ref "C58") (pin "2") (pinfunction "2_2") (pintype "passive"))
      (node (ref "C6") (pin "2") (pinfunction "2_2") (pintype "passive"))
      (node (ref "C61") (pin "2") (pinfunction "2_2") (pintype "passive"))
      (node (ref "C62") (pin "2") (pinfunction "2_2") (pintype "passive"))
      (node (ref "C63") (pin "2") (pinfunction "2_2") (pintype "passive"))
      (node (ref "C64") (pin "2") (pinfunction "2_2") (pintype "passive"))
      (node (ref "C65") (pin "2") (pinfunction "2_2") (pintype "passive"))
      (node (ref "C67") (pin "2") (pinfunction "2_2") (pintype "passive"))
      (node (ref "C68") (pin "2") (pinfunction "2_2") (pintype "passive"))
      (node (ref "C7") (pin "2") (pinfunction "2_2") (pintype "passive"))
      (node (ref "C72") (pin "2") (pinfunction "2_2") (pintype "passive"))
      (node (ref "C73") (pin "2") (pinfunction "2_2") (pintype "passive"))
      (node (ref "C74") (pin "2") (pinfunction "2_2") (pintype "passive"))
      (node (ref "C75") (pin "2") (pinfunction "2_2") (pintype "passive"))
      (node (ref "C76") (pin "2") (pinfunction "2_2") (pintype "passive"))
      (node (ref "C77") (pin "2") (pinfunction "2_2") (pintype "passive"))
      (node (ref "C78") (pin "2") (pinfunction "2_2") (pintype "passive"))
      (node (ref "C79") (pin "2") (pinfunction "2_2") (pintype "passive"))
      (node (ref "C8") (pin "2") (pinfunction "2_2") (pintype "passive"))
      (node (ref "C80") (pin "2") (pinfunction "2_2") (pintype "passive"))
      (node (ref "C81") (pin "2") (pinfunction "2_2") (pintype "passive"))
      (node (ref "C82") (pin "2") (pinfunction "2_2") (pintype "passive"))
      (node (ref "C83") (pin "2") (pinfunction "2_2") (pintype "passive"))
      (node (ref "C84") (pin "2") (pinfunction "2_2") (pintype "passive"))
      (node (ref "C85") (pin "2") (pinfunction "2_2") (pintype "passive"))
      (node (ref "C86") (pin "1") (pinfunction "1_1") (pintype "passive"))
      (node (ref "C87") (pin "2") (pinfunction "2_2") (pintype "passive"))
      (node (ref "C88") (pin "1") (pinfunction "1_1") (pintype "passive"))
      (node (ref "C9") (pin "2") (pinfunction "2_2") (pintype "passive"))
      (node (ref "C92") (pin "2") (pinfunction "2_2") (pintype "passive"))
      (node (ref "C93") (pin "2") (pinfunction "2_2") (pintype "passive"))
      (node (ref "C94") (pin "2") (pinfunction "2_2") (pintype "passive"))
      (node (ref "C95") (pin "2") (pinfunction "2_2") (pintype "passive"))
      (node (ref "C96") (pin "2") (pinfunction "2_2") (pintype "passive"))
      (node (ref "C97") (pin "2") (pinfunction "2_2") (pintype "passive"))
      (node (ref "C98") (pin "2") (pinfunction "2_2") (pintype "passive"))
      (node (ref "C99") (pin "2") (pinfunction "2_2") (pintype "passive"))
      (node (ref "FL2") (pin "1") (pinfunction "G1_1") (pintype "bidirectional"))
      (node (ref "FL2") (pin "3") (pinfunction "G2_3") (pintype "bidirectional"))
      (node (ref "FL2") (pin "4") (pinfunction "G3_4") (pintype "bidirectional"))
      (node (ref "FL2") (pin "5") (pinfunction "G4_5") (pintype "bidirectional"))
      (node (ref "FL2") (pin "7") (pinfunction "G6_7") (pintype "bidirectional"))
      (node (ref "FL2") (pin "8") (pinfunction "G5_8") (pintype "bidirectional"))
      (node (ref "FL3") (pin "1") (pinfunction "G6_1") (pintype "bidirectional"))
      (node (ref "FL3") (pin "3") (pinfunction "G5_3") (pintype "bidirectional"))
      (node (ref "FL3") (pin "4") (pinfunction "G4_4") (pintype "bidirectional"))
      (node (ref "FL3") (pin "5") (pinfunction "G3_5") (pintype "bidirectional"))
      (node (ref "FL3") (pin "7") (pinfunction "G2_7") (pintype "bidirectional"))
      (node (ref "FL3") (pin "8") (pinfunction "G1_8") (pintype "bidirectional"))
      (node (ref "G1") (pin "P$3") (pinfunction "1_P$3") (pintype "passive"))
      (node (ref "G1") (pin "P$4") (pinfunction "2_P$4") (pintype "passive"))
      (node (ref "IC1") (pin "2") (pinfunction "GND_2") (pintype "passive"))
      (node (ref "IC10") (pin "4") (pinfunction "GND_4") (pintype "power_in"))
      (node (ref "IC11") (pin "11") (pinfunction "FSYNC_11") (pintype "bidirectional"))
      (node (ref "IC11") (pin "18") (pinfunction "GND_18") (pintype "bidirectional"))
      (node (ref "IC11") (pin "20") (pinfunction "GND_20") (pintype "bidirectional"))
      (node (ref "IC11") (pin "9") (pinfunction "AD0/MISO_9") (pintype "bidirectional"))
      (node (ref "IC12") (pin "1") (pinfunction "A1_1") (pintype "bidirectional"))
      (node (ref "IC12") (pin "11") (pinfunction "GND_11") (pintype "bidirectional"))
      (node (ref "IC12") (pin "3") (pinfunction "A2_3") (pintype "bidirectional"))
      (node (ref "IC12") (pin "6") (pinfunction "A5_6") (pintype "bidirectional"))
      (node (ref "IC12") (pin "7") (pinfunction "A6_7") (pintype "bidirectional"))
      (node (ref "IC12") (pin "8") (pinfunction "A7_8") (pintype "bidirectional"))
      (node (ref "IC12") (pin "9") (pinfunction "A8_9") (pintype "bidirectional"))
      (node (ref "IC13") (pin "2") (pinfunction "GND_2") (pintype "input"))
      (node (ref "IC13") (pin "5") (pinfunction "WDR_5") (pintype "input"))
      (node (ref "IC14") (pin "2") (pinfunction "GND_2") (pintype "power_in"))
      (node (ref "IC14") (pin "3") (pinfunction "ADD1_3") (pintype "passive"))
      (node (ref "IC14") (pin "5") (pinfunction "ADD0_5") (pintype "passive"))
      (node (ref "IC15") (pin "GND1") (pinfunction "GND1_GND1") (pintype "bidirectional"))
      (node (ref "IC15") (pin "GND2") (pinfunction "GND2_GND2") (pintype "bidirectional"))
      (node (ref "IC16") (pin "4") (pinfunction "GND_4") (pintype "power_in"))
      (node (ref "IC16") (pin "5") (pinfunction "A2_5") (pintype "input"))
      (node (ref "IC16") (pin "6") (pinfunction "A1_6") (pintype "input"))
      (node (ref "IC16") (pin "EP") (pinfunction "GND_EP") (pintype "power_in"))
      (node (ref "IC17") (pin "10") (pinfunction "PDOWN_10") (pintype "input"))
      (node (ref "IC17") (pin "EXP") (pinfunction "GND_EXP") (pintype "power_in"))
      (node (ref "IC18") (pin "4") (pinfunction "GND_4") (pintype "power_in"))
      (node (ref "IC18") (pin "5") (pinfunction "A2_5") (pintype "input"))
      (node (ref "IC18") (pin "6") (pinfunction "A1_6") (pintype "input"))
      (node (ref "IC18") (pin "7") (pinfunction "A0_7") (pintype "input"))
      (node (ref "IC18") (pin "EP") (pinfunction "GND_EP") (pintype "power_in"))
      (node (ref "IC2") (pin "2") (pinfunction "GND_2") (pintype "passive"))
      (node (ref "IC3") (pin "6") (pinfunction "VSS_6") (pintype "bidirectional"))
      (node (ref "IC4") (pin "1") (pinfunction "GND_1") (pintype "input"))
      (node (ref "IC5") (pin "11") (pinfunction "GND_11") (pintype "bidirectional"))
      (node (ref "IC6") (pin "11") (pinfunction "GND_11") (pintype "bidirectional"))
      (node (ref "IC7") (pin "19") (pinfunction "LNA_P_19") (pintype "bidirectional"))
      (node (ref "IC7") (pin "20") (pinfunction "LNA_N_20") (pintype "bidirectional"))
      (node (ref "IC7") (pin "30") (pinfunction "XOSC_Q1_30") (pintype "bidirectional"))
      (node (ref "IC7") (pin "33") (pinfunction "GND_PAD_33") (pintype "bidirectional"))
      (node (ref "IC77") (pin "3") (pinfunction "GND_3") (pintype "power_in"))
      (node (ref "IC8") (pin "30") (pinfunction "XOSC_Q1_30") (pintype "bidirectional"))
      (node (ref "IC8") (pin "33") (pinfunction "GND_PAD_33") (pintype "bidirectional"))
      (node (ref "IC9") (pin "12") (pinfunction "GND_12") (pintype "bidirectional"))
      (node (ref "IC9") (pin "27") (pinfunction "GND_27") (pintype "bidirectional"))
      (node (ref "IC9") (pin "3") (pinfunction "GNDA_3") (pintype "bidirectional"))
      (node (ref "IC9") (pin "35") (pinfunction "GNDX_35") (pintype "bidirectional"))
      (node (ref "IC9") (pin "39") (pinfunction "GND_39") (pintype "bidirectional"))
      (node (ref "IC9") (pin "55") (pinfunction "GND_55") (pintype "bidirectional"))
      (node (ref "J1") (pin "2") (pinfunction "-_2") (pintype "bidirectional"))
      (node (ref "J2") (pin "2") (pinfunction "-_2") (pintype "bidirectional"))
      (node (ref "J3") (pin "3") (pinfunction "GND1_3") (pintype "power_in"))
      (node (ref "J3") (pin "5") (pinfunction "GND2_5") (pintype "power_in"))
      (node (ref "J3") (pin "9") (pinfunction "GNDD_9") (pintype "power_in"))
      (node (ref "JP1") (pin "2") (pinfunction "2_2") (pintype "passive"))
      (node (ref "JP5") (pin "2") (pinfunction "2_2") (pintype "passive"))
      (node (ref "JP6") (pin "2") (pinfunction "2_2") (pintype "passive"))
      (node (ref "JP7") (pin "2") (pinfunction "2_2") (pintype "passive"))
      (node (ref "JP8") (pin "P$2") (pinfunction "2_P$2") (pintype "passive"))
      (node (ref "JP8") (pin "P$3") (pinfunction "2_P$3") (pintype "passive"))
      (node (ref "JP8") (pin "P$4") (pinfunction "2_P$4") (pintype "passive"))
      (node (ref "JP8") (pin "P$5") (pinfunction "2_P$5") (pintype "passive"))
      (node (ref "JP9") (pin "P$2") (pinfunction "2_P$2") (pintype "passive"))
      (node (ref "JP9") (pin "P$3") (pinfunction "2_P$3") (pintype "passive"))
      (node (ref "JP9") (pin "P$4") (pinfunction "2_P$4") (pintype "passive"))
      (node (ref "JP9") (pin "P$5") (pinfunction "2_P$5") (pintype "passive"))
      (node (ref "L15") (pin "1") (pinfunction "P$1_1") (pintype "passive"))
      (node (ref "L6") (pin "1") (pinfunction "P$1_1") (pintype "passive"))
      (node (ref "LED1") (pin "C") (pinfunction "C_C") (pintype "passive"))
      (node (ref "LED2") (pin "C") (pinfunction "C_C") (pintype "passive"))
      (node (ref "LED4") (pin "C") (pinfunction "C_C") (pintype "passive"))
      (node (ref "LED5") (pin "C") (pinfunction "C_C") (pintype "passive"))
      (node (ref "LED6") (pin "C") (pinfunction "C_C") (pintype "passive"))
      (node (ref "LED7") (pin "C") (pinfunction "C_C") (pintype "passive"))
      (node (ref "LED8") (pin "C") (pinfunction "C_C") (pintype "passive"))
      (node (ref "Q4") (pin "2") (pinfunction "S_2") (pintype "passive"))
      (node (ref "R11") (pin "2") (pinfunction "P$2_2") (pintype "passive"))
      (node (ref "R12") (pin "2") (pinfunction "P$2_2") (pintype "passive"))
      (node (ref "R25") (pin "1") (pinfunction "P$1_1") (pintype "passive"))
      (node (ref "SV3") (pin "29") (pinfunction "29_29") (pintype "passive"))
      (node (ref "SV3") (pin "30") (pinfunction "30_30") (pintype "passive"))
      (node (ref "SV3") (pin "31") (pinfunction "31_31") (pintype "passive"))
      (node (ref "SV3") (pin "32") (pinfunction "32_32") (pintype "passive"))
      (node (ref "TP25") (pin "TP") (pinfunction "TP_TP") (pintype "input"))
      (node (ref "X1") (pin "G1") (pinfunction "G_G1") (pintype "passive"))
      (node (ref "X1") (pin "G10") (pinfunction "G_G10") (pintype "passive"))
      (node (ref "X1") (pin "G11") (pinfunction "G_G11") (pintype "passive"))
      (node (ref "X1") (pin "G12") (pinfunction "G_G12") (pintype "passive"))
      (node (ref "X1") (pin "G13") (pinfunction "G_G13") (pintype "passive"))
      (node (ref "X1") (pin "G14") (pinfunction "G_G14") (pintype "passive"))
      (node (ref "X1") (pin "G15") (pinfunction "G_G15") (pintype "passive"))
      (node (ref "X1") (pin "G16") (pinfunction "G_G16") (pintype "passive"))
      (node (ref "X1") (pin "G17") (pinfunction "G_G17") (pintype "passive"))
      (node (ref "X1") (pin "G19") (pinfunction "G_G19") (pintype "passive"))
      (node (ref "X1") (pin "G2") (pinfunction "G_G2") (pintype "passive"))
      (node (ref "X1") (pin "G20") (pinfunction "G_G20") (pintype "passive"))
      (node (ref "X1") (pin "G21") (pinfunction "G_G21") (pintype "passive"))
      (node (ref "X1") (pin "G3") (pinfunction "G_G3") (pintype "passive"))
      (node (ref "X1") (pin "G4") (pinfunction "G_G4") (pintype "passive"))
      (node (ref "X1") (pin "G5") (pinfunction "G_G5") (pintype "passive"))
      (node (ref "X1") (pin "G6") (pinfunction "G_G6") (pintype "passive"))
      (node (ref "X1") (pin "G7") (pinfunction "G_G7") (pintype "passive"))
      (node (ref "X1") (pin "G8") (pinfunction "G_G8") (pintype "passive"))
      (node (ref "X1") (pin "G9") (pinfunction "G_G9") (pintype "passive"))
      (node (ref "X2") (pin "G1") (pinfunction "G_G1") (pintype "passive"))
      (node (ref "X2") (pin "G10") (pinfunction "G_G10") (pintype "passive"))
      (node (ref "X2") (pin "G11") (pinfunction "G_G11") (pintype "passive"))
      (node (ref "X2") (pin "G12") (pinfunction "G_G12") (pintype "passive"))
      (node (ref "X2") (pin "G13") (pinfunction "G_G13") (pintype "passive"))
      (node (ref "X2") (pin "G14") (pinfunction "G_G14") (pintype "passive"))
      (node (ref "X2") (pin "G15") (pinfunction "G_G15") (pintype "passive"))
      (node (ref "X2") (pin "G16") (pinfunction "G_G16") (pintype "passive"))
      (node (ref "X2") (pin "G17") (pinfunction "G_G17") (pintype "passive"))
      (node (ref "X2") (pin "G19") (pinfunction "G_G19") (pintype "passive"))
      (node (ref "X2") (pin "G2") (pinfunction "G_G2") (pintype "passive"))
      (node (ref "X2") (pin "G20") (pinfunction "G_G20") (pintype "passive"))
      (node (ref "X2") (pin "G21") (pinfunction "G_G21") (pintype "passive"))
      (node (ref "X2") (pin "G3") (pinfunction "G_G3") (pintype "passive"))
      (node (ref "X2") (pin "G4") (pinfunction "G_G4") (pintype "passive"))
      (node (ref "X2") (pin "G5") (pinfunction "G_G5") (pintype "passive"))
      (node (ref "X2") (pin "G6") (pinfunction "G_G6") (pintype "passive"))
      (node (ref "X2") (pin "G7") (pinfunction "G_G7") (pintype "passive"))
      (node (ref "X2") (pin "G8") (pinfunction "G_G8") (pintype "passive"))
      (node (ref "X2") (pin "G9") (pinfunction "G_G9") (pintype "passive"))
      (node (ref "X3") (pin "1") (pinfunction "GND_1") (pintype "power_in"))
      (node (ref "X3") (pin "3") (pinfunction "GND_3") (pintype "power_in"))
      (node (ref "X4") (pin "1") (pinfunction "GND_1") (pintype "power_in"))
      (node (ref "X4") (pin "3") (pinfunction "GND_3") (pintype "power_in"))
      (node (ref "X5") (pin "G1") (pinfunction "G_G1") (pintype "passive"))
      (node (ref "X5") (pin "G10") (pinfunction "G_G10") (pintype "passive"))
      (node (ref "X5") (pin "G11") (pinfunction "G_G11") (pintype "passive"))
      (node (ref "X5") (pin "G12") (pinfunction "G_G12") (pintype "passive"))
      (node (ref "X5") (pin "G13") (pinfunction "G_G13") (pintype "passive"))
      (node (ref "X5") (pin "G14") (pinfunction "G_G14") (pintype "passive"))
      (node (ref "X5") (pin "G15") (pinfunction "G_G15") (pintype "passive"))
      (node (ref "X5") (pin "G16") (pinfunction "G_G16") (pintype "passive"))
      (node (ref "X5") (pin "G17") (pinfunction "G_G17") (pintype "passive"))
      (node (ref "X5") (pin "G19") (pinfunction "G_G19") (pintype "passive"))
      (node (ref "X5") (pin "G2") (pinfunction "G_G2") (pintype "passive"))
      (node (ref "X5") (pin "G20") (pinfunction "G_G20") (pintype "passive"))
      (node (ref "X5") (pin "G21") (pinfunction "G_G21") (pintype "passive"))
      (node (ref "X5") (pin "G3") (pinfunction "G_G3") (pintype "passive"))
      (node (ref "X5") (pin "G4") (pinfunction "G_G4") (pintype "passive"))
      (node (ref "X5") (pin "G5") (pinfunction "G_G5") (pintype "passive"))
      (node (ref "X5") (pin "G6") (pinfunction "G_G6") (pintype "passive"))
      (node (ref "X5") (pin "G7") (pinfunction "G_G7") (pintype "passive"))
      (node (ref "X5") (pin "G8") (pinfunction "G_G8") (pintype "passive"))
      (node (ref "X5") (pin "G9") (pinfunction "G_G9") (pintype "passive"))
      (node (ref "X6") (pin "G1") (pinfunction "G_G1") (pintype "passive"))
      (node (ref "X6") (pin "G10") (pinfunction "G_G10") (pintype "passive"))
      (node (ref "X6") (pin "G11") (pinfunction "G_G11") (pintype "passive"))
      (node (ref "X6") (pin "G12") (pinfunction "G_G12") (pintype "passive"))
      (node (ref "X6") (pin "G13") (pinfunction "G_G13") (pintype "passive"))
      (node (ref "X6") (pin "G14") (pinfunction "G_G14") (pintype "passive"))
      (node (ref "X6") (pin "G15") (pinfunction "G_G15") (pintype "passive"))
      (node (ref "X6") (pin "G16") (pinfunction "G_G16") (pintype "passive"))
      (node (ref "X6") (pin "G17") (pinfunction "G_G17") (pintype "passive"))
      (node (ref "X6") (pin "G19") (pinfunction "G_G19") (pintype "passive"))
      (node (ref "X6") (pin "G2") (pinfunction "G_G2") (pintype "passive"))
      (node (ref "X6") (pin "G20") (pinfunction "G_G20") (pintype "passive"))
      (node (ref "X6") (pin "G21") (pinfunction "G_G21") (pintype "passive"))
      (node (ref "X6") (pin "G3") (pinfunction "G_G3") (pintype "passive"))
      (node (ref "X6") (pin "G4") (pinfunction "G_G4") (pintype "passive"))
      (node (ref "X6") (pin "G5") (pinfunction "G_G5") (pintype "passive"))
      (node (ref "X6") (pin "G6") (pinfunction "G_G6") (pintype "passive"))
      (node (ref "X6") (pin "G7") (pinfunction "G_G7") (pintype "passive"))
      (node (ref "X6") (pin "G8") (pinfunction "G_G8") (pintype "passive"))
      (node (ref "X6") (pin "G9") (pinfunction "G_G9") (pintype "passive"))
    )
    (net (code "13") (name "GNSS{slash}PV") (class "Default")
      (node (ref "IC9") (pin "7") (pinfunction "PE2_7") (pintype "bidirectional"))
      (node (ref "SV2") (pin "22") (pinfunction "22_22") (pintype "passive"))
    )
    (net (code "14") (name "GNSS{slash}RXD") (class "Default")
      (node (ref "IC9") (pin "18") (pinfunction "PA1/U0TX_18") (pintype "bidirectional"))
      (node (ref "SV2") (pin "15") (pinfunction "15_15") (pintype "passive"))
    )
    (net (code "15") (name "GNSS{slash}TXD") (class "Default")
      (node (ref "IC9") (pin "17") (pinfunction "PA0/U0RX_17") (pintype "bidirectional"))
      (node (ref "SV2") (pin "16") (pinfunction "16_16") (pintype "passive"))
    )
    (net (code "16") (name "GNSS{slash}~{RESETIN}") (class "Default")
      (node (ref "IC9") (pin "6") (pinfunction "PE3_6") (pintype "bidirectional"))
      (node (ref "SV2") (pin "10") (pinfunction "10_10") (pintype "passive"))
    )
    (net (code "17") (name "GPIO1") (class "Default")
      (node (ref "IC9") (pin "16") (pinfunction "PC4_16") (pintype "bidirectional"))
      (node (ref "SV2") (pin "1") (pinfunction "1_1") (pintype "passive"))
    )
    (net (code "18") (name "GPIO2") (class "Default")
      (node (ref "IC9") (pin "43") (pinfunction "PD4_43") (pintype "bidirectional"))
      (node (ref "SV2") (pin "2") (pinfunction "2_2") (pintype "passive"))
    )
    (net (code "19") (name "GPIO3") (class "Default")
      (node (ref "IC9") (pin "44") (pinfunction "PD5_44") (pintype "bidirectional"))
      (node (ref "SV3") (pin "1") (pinfunction "1_1") (pintype "passive"))
    )
    (net (code "20") (name "GPIO4") (class "Default")
      (node (ref "IC9") (pin "45") (pinfunction "PB0/USB0ID_45") (pintype "bidirectional"))
      (node (ref "SV3") (pin "2") (pinfunction "2_2") (pintype "passive"))
    )
    (net (code "21") (name "GPIO5") (class "Default")
      (node (ref "IC9") (pin "15") (pinfunction "PC5_15") (pintype "bidirectional"))
      (node (ref "SV3") (pin "5") (pinfunction "5_5") (pintype "passive"))
    )
    (net (code "22") (name "Net-(C62-Pad1)") (class "Default")
      (node (ref "C62") (pin "1") (pinfunction "1_1") (pintype "passive"))
      (node (ref "C63") (pin "1") (pinfunction "1_1") (pintype "passive"))
      (node (ref "C64") (pin "1") (pinfunction "1_1") (pintype "passive"))
      (node (ref "C65") (pin "1") (pinfunction "1_1") (pintype "passive"))
      (node (ref "IC9") (pin "25") (pinfunction "VDDC_25") (pintype "bidirectional"))
      (node (ref "IC9") (pin "56") (pinfunction "VDDC_56") (pintype "bidirectional"))
    )
    (net (code "23") (name "Net-(C91-Pad2)") (class "Default")
      (node (ref "C91") (pin "2") (pinfunction "2_2") (pintype "passive"))
      (node (ref "IC15") (pin "RF_IN") (pinfunction "RF_IN_RF_IN") (pintype "bidirectional"))
    )
    (net (code "24") (name "Net-(FL2-RF_IN)") (class "Default")
      (node (ref "FL2") (pin "2") (pinfunction "RF_IN_2") (pintype "bidirectional"))
      (node (ref "JP9") (pin "P$1") (pinfunction "1_P$1") (pintype "passive"))
    )
    (net (code "25") (name "Net-(FL2-RF_OUT)") (class "Default")
      (node (ref "C60") (pin "2") (pinfunction "2_2") (pintype "passive"))
      (node (ref "FL2") (pin "6") (pinfunction "RF_OUT_6") (pintype "bidirectional"))
    )
    (net (code "26") (name "Net-(FL3-RF_IN)") (class "Default")
      (node (ref "C88") (pin "2") (pinfunction "2_2") (pintype "passive"))
      (node (ref "C90") (pin "2") (pinfunction "2_2") (pintype "passive"))
      (node (ref "FL3") (pin "2") (pinfunction "RF_IN_2") (pintype "bidirectional"))
    )
    (net (code "27") (name "Net-(FL3-RF_OUT)") (class "Default")
      (node (ref "FL3") (pin "6") (pinfunction "RF_OUT_6") (pintype "bidirectional"))
      (node (ref "JP8") (pin "P$1") (pinfunction "1_P$1") (pintype "passive"))
    )
    (net (code "28") (name "Net-(IC1-IN)") (class "Default")
      (node (ref "C6") (pin "1") (pinfunction "1_1") (pintype "passive"))
      (node (ref "IC1") (pin "1") (pinfunction "IN_1") (pintype "power_in"))
      (node (ref "JP3") (pin "1") (pinfunction "1_1") (pintype "passive"))
      (node (ref "R1") (pin "2") (pinfunction "P$2_2") (pintype "passive"))
      (node (ref "R2") (pin "2") (pinfunction "P$2_2") (pintype "passive"))
    )
    (net (code "29") (name "Net-(IC1-NR)") (class "Default")
      (node (ref "C1") (pin "1") (pinfunction "1_1") (pintype "passive"))
      (node (ref "IC1") (pin "4") (pinfunction "NR_4") (pintype "input"))
    )
    (net (code "30") (name "Net-(IC1-OUT)") (class "Default")
      (node (ref "C13") (pin "1") (pinfunction "1_1") (pintype "passive"))
      (node (ref "C18") (pin "1") (pinfunction "1_1") (pintype "passive"))
      (node (ref "C19") (pin "2") (pinfunction "2_2") (pintype "passive"))
      (node (ref "C20") (pin "2") (pinfunction "2_2") (pintype "passive"))
      (node (ref "C27") (pin "2") (pinfunction "2_2") (pintype "passive"))
      (node (ref "C29") (pin "2") (pinfunction "2_2") (pintype "passive"))
      (node (ref "C3") (pin "1") (pinfunction "1_1") (pintype "passive"))
      (node (ref "C30") (pin "2") (pinfunction "2_2") (pintype "passive"))
      (node (ref "C33") (pin "2") (pinfunction "2_2") (pintype "passive"))
      (node (ref "C34") (pin "2") (pinfunction "2_2") (pintype "passive"))
      (node (ref "C36") (pin "2") (pinfunction "2_2") (pintype "passive"))
      (node (ref "C43") (pin "2") (pinfunction "2_2") (pintype "passive"))
      (node (ref "C44") (pin "2") (pinfunction "2_2") (pintype "passive"))
      (node (ref "C52") (pin "2") (pinfunction "2_2") (pintype "passive"))
      (node (ref "IC1") (pin "5") (pinfunction "OUT_5") (pintype "output"))
      (node (ref "IC5") (pin "2") (pinfunction "VCCA_2") (pintype "bidirectional"))
      (node (ref "IC8") (pin "1") (pinfunction "VDD_GUARD_1") (pintype "bidirectional"))
      (node (ref "IC8") (pin "12") (pinfunction "DVDD_2_12") (pintype "bidirectional"))
      (node (ref "IC8") (pin "13") (pinfunction "AVDD_IF_13") (pintype "bidirectional"))
      (node (ref "IC8") (pin "15") (pinfunction "AVDD_RF_15") (pintype "bidirectional"))
      (node (ref "IC8") (pin "22") (pinfunction "AVDD_SYNTH_1_22") (pintype "bidirectional"))
      (node (ref "IC8") (pin "25") (pinfunction "AVDD_PFD_CHP_25") (pintype "bidirectional"))
      (node (ref "IC8") (pin "26") (pinfunction "DCPL_PFD_CHIP_26") (pintype "bidirectional"))
      (node (ref "IC8") (pin "27") (pinfunction "AVDD_SYNTH2_27") (pintype "bidirectional"))
      (node (ref "IC8") (pin "28") (pinfunction "AVDD_XOSC_28") (pintype "bidirectional"))
      (node (ref "IC8") (pin "29") (pinfunction "DCPL_XOSC_29") (pintype "bidirectional"))
      (node (ref "IC8") (pin "5") (pinfunction "DVDD_1_5") (pintype "bidirectional"))
      (node (ref "R10") (pin "2") (pinfunction "P$2_2") (pintype "passive"))
      (node (ref "R5") (pin "1") (pinfunction "P$1_1") (pintype "passive"))
      (node (ref "R9") (pin "2") (pinfunction "P$2_2") (pintype "passive"))
      (node (ref "X4") (pin "6") (pinfunction "VCC_6") (pintype "power_in"))
    )
    (net (code "31") (name "Net-(IC2-IN)") (class "Default")
      (node (ref "C7") (pin "1") (pinfunction "1_1") (pintype "passive"))
      (node (ref "IC2") (pin "1") (pinfunction "IN_1") (pintype "power_in"))
      (node (ref "JP2") (pin "2") (pinfunction "2_2") (pintype "passive"))
      (node (ref "R3") (pin "2") (pinfunction "P$2_2") (pintype "passive"))
      (node (ref "R4") (pin "2") (pinfunction "P$2_2") (pintype "passive"))
    )
    (net (code "32") (name "Net-(IC2-NR)") (class "Default")
      (node (ref "C2") (pin "1") (pinfunction "1_1") (pintype "passive"))
      (node (ref "IC2") (pin "4") (pinfunction "NR_4") (pintype "input"))
    )
    (net (code "33") (name "Net-(IC2-OUT)") (class "Default")
      (node (ref "C12") (pin "1") (pinfunction "1_1") (pintype "passive"))
      (node (ref "C14") (pin "1") (pinfunction "1_1") (pintype "passive"))
      (node (ref "C15") (pin "2") (pinfunction "2_2") (pintype "passive"))
      (node (ref "C16") (pin "2") (pinfunction "2_2") (pintype "passive"))
      (node (ref "C23") (pin "2") (pinfunction "2_2") (pintype "passive"))
      (node (ref "C25") (pin "2") (pinfunction "2_2") (pintype "passive"))
      (node (ref "C26") (pin "2") (pinfunction "2_2") (pintype "passive"))
      (node (ref "C28") (pin "2") (pinfunction "2_2") (pintype "passive"))
      (node (ref "C31") (pin "2") (pinfunction "2_2") (pintype "passive"))
      (node (ref "C32") (pin "2") (pinfunction "2_2") (pintype "passive"))
      (node (ref "C35") (pin "2") (pinfunction "2_2") (pintype "passive"))
      (node (ref "C37") (pin "1") (pinfunction "1_1") (pintype "passive"))
      (node (ref "C4") (pin "1") (pinfunction "1_1") (pintype "passive"))
      (node (ref "C40") (pin "2") (pinfunction "2_2") (pintype "passive"))
      (node (ref "C46") (pin "2") (pinfunction "2_2") (pintype "passive"))
      (node (ref "C48") (pin "1") (pinfunction "1_1") (pintype "passive"))
      (node (ref "C49") (pin "1") (pinfunction "1_1") (pintype "passive"))
      (node (ref "C5") (pin "1") (pinfunction "1_1") (pintype "passive"))
      (node (ref "C9") (pin "1") (pinfunction "1_1") (pintype "passive"))
      (node (ref "C93") (pin "1") (pinfunction "1_1") (pintype "passive"))
      (node (ref "IC2") (pin "5") (pinfunction "OUT_5") (pintype "output"))
      (node (ref "IC3") (pin "5") (pinfunction "VCC_5") (pintype "bidirectional"))
      (node (ref "IC6") (pin "2") (pinfunction "VCCA_2") (pintype "bidirectional"))
      (node (ref "IC7") (pin "1") (pinfunction "VDD_GUARD_1") (pintype "bidirectional"))
      (node (ref "IC7") (pin "12") (pinfunction "DVDD_2_12") (pintype "bidirectional"))
      (node (ref "IC7") (pin "13") (pinfunction "AVDD_IF_13") (pintype "bidirectional"))
      (node (ref "IC7") (pin "15") (pinfunction "AVDD_RF_15") (pintype "bidirectional"))
      (node (ref "IC7") (pin "22") (pinfunction "AVDD_SYNTH_1_22") (pintype "bidirectional"))
      (node (ref "IC7") (pin "25") (pinfunction "AVDD_PFD_CHP_25") (pintype "bidirectional"))
      (node (ref "IC7") (pin "26") (pinfunction "DCPL_PFD_CHIP_26") (pintype "bidirectional"))
      (node (ref "IC7") (pin "27") (pinfunction "AVDD_SYNTH2_27") (pintype "bidirectional"))
      (node (ref "IC7") (pin "28") (pinfunction "AVDD_XOSC_28") (pintype "bidirectional"))
      (node (ref "IC7") (pin "29") (pinfunction "DCPL_XOSC_29") (pintype "bidirectional"))
      (node (ref "IC7") (pin "5") (pinfunction "DVDD_1_5") (pintype "bidirectional"))
      (node (ref "IC77") (pin "5") (pinfunction "+V_5") (pintype "power_in"))
      (node (ref "JP1") (pin "1") (pinfunction "1_1") (pintype "passive"))
      (node (ref "R13") (pin "2") (pinfunction "P$2_2") (pintype "passive"))
      (node (ref "R6") (pin "1") (pinfunction "P$1_1") (pintype "passive"))
      (node (ref "R7") (pin "2") (pinfunction "P$2_2") (pintype "passive"))
      (node (ref "R8") (pin "2") (pinfunction "P$2_2") (pintype "passive"))
      (node (ref "X3") (pin "6") (pinfunction "VCC_6") (pintype "power_in"))
    )
    (net (code "34") (name "Net-(IC3-P1.6)") (class "Default")
      (node (ref "IC3") (pin "11") (pinfunction "P1.6_11") (pintype "bidirectional"))
      (node (ref "TP24") (pin "TP") (pinfunction "TP_TP") (pintype "input"))
    )
    (net (code "35") (name "Net-(IC3-P1.7)") (class "Default")
      (node (ref "IC3") (pin "10") (pinfunction "P1.7_10") (pintype "bidirectional"))
      (node (ref "TP23") (pin "TP") (pinfunction "TP_TP") (pintype "input"))
    )
    (net (code "36") (name "Net-(IC3-P2.0)") (class "Default")
      (node (ref "IC3") (pin "9") (pinfunction "P2.0_9") (pintype "bidirectional"))
      (node (ref "R16") (pin "2") (pinfunction "P$2_2") (pintype "passive"))
    )
    (net (code "37") (name "Net-(IC3-TEST)") (class "Default")
      (node (ref "IC3") (pin "3") (pinfunction "TEST_3") (pintype "bidirectional"))
      (node (ref "JP1") (pin "3") (pinfunction "3_3") (pintype "passive"))
    )
    (net (code "38") (name "Net-(IC3-~{RST})") (class "Default")
      (node (ref "IC3") (pin "4") (pinfunction "~{RST}_4") (pintype "bidirectional"))
      (node (ref "JP1") (pin "4") (pinfunction "4_4") (pintype "passive"))
    )
    (net (code "39") (name "Net-(IC4-OUT)") (class "Default")
      (node (ref "C11") (pin "1") (pinfunction "1_1") (pintype "passive"))
      (node (ref "IC4") (pin "2") (pinfunction "OUT_2") (pintype "passive"))
      (node (ref "SJ3") (pin "1") (pinfunction "1_1") (pintype "passive"))
    )
    (net (code "40") (name "Net-(IC5-OE)") (class "Default")
      (node (ref "IC5") (pin "10") (pinfunction "OE_10") (pintype "bidirectional"))
      (node (ref "JP6") (pin "1") (pinfunction "1_1") (pintype "passive"))
      (node (ref "R9") (pin "1") (pinfunction "P$1_1") (pintype "passive"))
    )
    (net (code "41") (name "Net-(IC6-OE)") (class "Default")
      (node (ref "IC6") (pin "10") (pinfunction "OE_10") (pintype "bidirectional"))
      (node (ref "JP5") (pin "1") (pinfunction "1_1") (pintype "passive"))
      (node (ref "R8") (pin "1") (pinfunction "P$1_1") (pintype "passive"))
    )
    (net (code "42") (name "Net-(IC7-DCPL)") (class "Default")
      (node (ref "C17") (pin "1") (pinfunction "1_1") (pintype "passive"))
      (node (ref "IC7") (pin "6") (pinfunction "DCPL_6") (pintype "bidirectional"))
    )
    (net (code "43") (name "Net-(IC7-DCPL_VCO)") (class "Default")
      (node (ref "C53") (pin "1") (pinfunction "1_1") (pintype "passive"))
      (node (ref "IC7") (pin "21") (pinfunction "DCPL_VCO_21") (pintype "bidirectional"))
    )
    (net (code "44") (name "Net-(IC7-EXT_XOSC)") (class "Default")
      (node (ref "C22") (pin "2") (pinfunction "2_2") (pintype "passive"))
      (node (ref "IC7") (pin "32") (pinfunction "EXT_XOSC_32") (pintype "bidirectional"))
    )
    (net (code "45") (name "Net-(IC7-LPF0)") (class "Default")
      (node (ref "C41") (pin "1") (pinfunction "1_1") (pintype "passive"))
      (node (ref "IC7") (pin "23") (pinfunction "LPF0_23") (pintype "bidirectional"))
    )
    (net (code "46") (name "Net-(IC7-LPF1)") (class "Default")
      (node (ref "C41") (pin "2") (pinfunction "2_2") (pintype "passive"))
      (node (ref "IC7") (pin "24") (pinfunction "LPF1_24") (pintype "bidirectional"))
    )
    (net (code "47") (name "Net-(IC7-PA)") (class "Default")
      (node (ref "C42") (pin "1") (pinfunction "1_1") (pintype "passive"))
      (node (ref "IC7") (pin "17") (pinfunction "PA_17") (pintype "bidirectional"))
      (node (ref "L1") (pin "1") (pinfunction "P$1_1") (pintype "passive"))
    )
    (net (code "48") (name "Net-(IC7-RBIAS)") (class "Default")
      (node (ref "IC7") (pin "14") (pinfunction "RBIAS_14") (pintype "bidirectional"))
      (node (ref "R11") (pin "1") (pinfunction "P$1_1") (pintype "passive"))
    )
    (net (code "49") (name "Net-(IC7-TRX_SW)") (class "Default")
      (node (ref "IC7") (pin "18") (pinfunction "TRX_SW_18") (pintype "bidirectional"))
      (node (ref "TP3") (pin "TP") (pinfunction "TP_TP") (pintype "input"))
    )
    (net (code "50") (name "Net-(IC8-DCPL)") (class "Default")
      (node (ref "C21") (pin "1") (pinfunction "1_1") (pintype "passive"))
      (node (ref "IC8") (pin "6") (pinfunction "DCPL_6") (pintype "bidirectional"))
    )
    (net (code "51") (name "Net-(IC8-DCPL_VCO)") (class "Default")
      (node (ref "C55") (pin "1") (pinfunction "1_1") (pintype "passive"))
      (node (ref "IC8") (pin "21") (pinfunction "DCPL_VCO_21") (pintype "bidirectional"))
    )
    (net (code "52") (name "Net-(IC8-EXT_XOSC)") (class "Default")
      (node (ref "C24") (pin "2") (pinfunction "2_2") (pintype "passive"))
      (node (ref "IC8") (pin "32") (pinfunction "EXT_XOSC_32") (pintype "bidirectional"))
    )
    (net (code "53") (name "Net-(IC8-LNA_N)") (class "Default")
      (node (ref "C57") (pin "1") (pinfunction "1_1") (pintype "passive"))
      (node (ref "IC8") (pin "20") (pinfunction "LNA_N_20") (pintype "bidirectional"))
      (node (ref "L3") (pin "1") (pinfunction "P$1_1") (pintype "passive"))
      (node (ref "L6") (pin "2") (pinfunction "P$2_2") (pintype "passive"))
    )
    (net (code "54") (name "Net-(IC8-LNA_P)") (class "Default")
      (node (ref "C58") (pin "1") (pinfunction "1_1") (pintype "passive"))
      (node (ref "IC8") (pin "19") (pinfunction "LNA_P_19") (pintype "bidirectional"))
      (node (ref "L3") (pin "2") (pinfunction "P$2_2") (pintype "passive"))
      (node (ref "L7") (pin "1") (pinfunction "P$1_1") (pintype "passive"))
    )
    (net (code "55") (name "Net-(IC8-LPF0)") (class "Default")
      (node (ref "C45") (pin "1") (pinfunction "1_1") (pintype "passive"))
      (node (ref "IC8") (pin "23") (pinfunction "LPF0_23") (pintype "bidirectional"))
    )
    (net (code "56") (name "Net-(IC8-LPF1)") (class "Default")
      (node (ref "C45") (pin "2") (pinfunction "2_2") (pintype "passive"))
      (node (ref "IC8") (pin "24") (pinfunction "LPF1_24") (pintype "bidirectional"))
    )
    (net (code "57") (name "Net-(IC8-RBIAS)") (class "Default")
      (node (ref "IC8") (pin "14") (pinfunction "RBIAS_14") (pintype "bidirectional"))
      (node (ref "R12") (pin "1") (pinfunction "P$1_1") (pintype "passive"))
    )
    (net (code "58") (name "Net-(IC9-OSC0)") (class "Default")
      (node (ref "C77") (pin "1") (pinfunction "1_1") (pintype "passive"))
      (node (ref "IC9") (pin "40") (pinfunction "OSC0_40") (pintype "bidirectional"))
      (node (ref "Y1") (pin "1") (pinfunction "1_1") (pintype "passive"))
    )
    (net (code "59") (name "Net-(IC9-OSC1)") (class "Default")
      (node (ref "C76") (pin "1") (pinfunction "1_1") (pintype "passive"))
      (node (ref "IC9") (pin "41") (pinfunction "OSC1_41") (pintype "bidirectional"))
      (node (ref "Y1") (pin "3") (pinfunction "2_3") (pintype "passive"))
    )
    (net (code "60") (name "Net-(IC9-PB1{slash}USB0VBUS)") (class "Default")
      (node (ref "IC9") (pin "46") (pinfunction "PB1/USB0VBUS_46") (pintype "bidirectional"))
      (node (ref "R30") (pin "2") (pinfunction "P$2_2") (pintype "passive"))
    )
    (net (code "61") (name "Net-(IC9-PC2{slash}TDI)") (class "Default")
      (node (ref "IC9") (pin "50") (pinfunction "PC2/TDI_50") (pintype "bidirectional"))
      (node (ref "R31") (pin "2") (pinfunction "P$2_2") (pintype "passive"))
    )
    (net (code "62") (name "Net-(IC9-XOSC0)") (class "Default")
      (node (ref "C75") (pin "1") (pinfunction "1_1") (pintype "passive"))
      (node (ref "IC9") (pin "34") (pinfunction "XOSC0_34") (pintype "bidirectional"))
      (node (ref "Q3") (pin "P$2") (pinfunction "2_P$2") (pintype "bidirectional"))
    )
    (net (code "63") (name "Net-(IC9-XOSC1)") (class "Default")
      (node (ref "C74") (pin "1") (pinfunction "1_1") (pintype "passive"))
      (node (ref "IC9") (pin "36") (pinfunction "XOSC1_36") (pintype "bidirectional"))
      (node (ref "Q3") (pin "P$1") (pinfunction "1_P$1") (pintype "bidirectional"))
    )
    (net (code "64") (name "Net-(IC9-~{WAKE})") (class "Default")
      (node (ref "IC9") (pin "32") (pinfunction "~{WAKE}_32") (pintype "bidirectional"))
      (node (ref "R14") (pin "1") (pinfunction "P$1_1") (pintype "passive"))
    )
    (net (code "65") (name "Net-(IC11-REGOUT)") (class "Default")
      (node (ref "C80") (pin "1") (pinfunction "1_1") (pintype "passive"))
      (node (ref "IC11") (pin "10") (pinfunction "REGOUT_10") (pintype "bidirectional"))
    )
    (net (code "66") (name "Net-(IC12-A3)") (class "Default")
      (node (ref "IC12") (pin "4") (pinfunction "A3_4") (pintype "bidirectional"))
      (node (ref "IC9") (pin "13") (pinfunction "PC7_13") (pintype "bidirectional"))
    )
    (net (code "67") (name "Net-(IC12-A4)") (class "Default")
      (node (ref "IC12") (pin "5") (pinfunction "A4_5") (pintype "bidirectional"))
      (node (ref "IC9") (pin "14") (pinfunction "PC6_14") (pintype "bidirectional"))
    )
    (net (code "68") (name "Net-(IC12-B3)") (class "Default")
      (node (ref "IC12") (pin "17") (pinfunction "B3_17") (pintype "bidirectional"))
      (node (ref "R17") (pin "2") (pinfunction "P$2_2") (pintype "passive"))
    )
    (net (code "69") (name "Net-(IC12-B4)") (class "Default")
      (node (ref "IC12") (pin "16") (pinfunction "B4_16") (pintype "bidirectional"))
      (node (ref "R18") (pin "2") (pinfunction "P$2_2") (pintype "passive"))
    )
    (net (code "70") (name "Net-(IC17-IN)") (class "Default")
      (node (ref "C100") (pin "1") (pinfunction "1_1") (pintype "passive"))
      (node (ref "IC17") (pin "3") (pinfunction "IN_3") (pintype "input"))
      (node (ref "L17") (pin "2") (pinfunction "P$2_2") (pintype "passive"))
    )
    (net (code "71") (name "Net-(IC17-VBA1)") (class "Default")
      (node (ref "IC17") (pin "1") (pinfunction "VBA1_1") (pintype "input"))
      (node (ref "R27") (pin "2") (pinfunction "P$2_2") (pintype "passive"))
    )
    (net (code "72") (name "Net-(IC17-VBA2)") (class "Default")
      (node (ref "IC17") (pin "12") (pinfunction "VBA2_12") (pintype "input"))
      (node (ref "R26") (pin "2") (pinfunction "P$2_2") (pintype "passive"))
    )
    (net (code "73") (name "Net-(IC17-VCC1)") (class "Default")
      (node (ref "C97") (pin "1") (pinfunction "1_1") (pintype "passive"))
      (node (ref "IC17") (pin "11") (pinfunction "VCC1_11") (pintype "passive"))
      (node (ref "L14") (pin "1") (pinfunction "P$1_1") (pintype "passive"))
    )
    (net (code "74") (name "Net-(IC77-Y)") (class "Default")
      (node (ref "IC77") (pin "4") (pinfunction "Y_4") (pintype "output"))
      (node (ref "Q4") (pin "1") (pinfunction "G_1") (pintype "passive"))
      (node (ref "R25") (pin "2") (pinfunction "P$2_2") (pintype "passive"))
    )
    (net (code "75") (name "Net-(L1-P$2)") (class "Default")
      (node (ref "C37") (pin "2") (pinfunction "2_2") (pintype "passive"))
      (node (ref "L1") (pin "2") (pinfunction "P$2_2") (pintype "passive"))
      (node (ref "R13") (pin "1") (pinfunction "P$1_1") (pintype "passive"))
    )
    (net (code "76") (name "Net-(L2-P$1)") (class "Default")
      (node (ref "C42") (pin "2") (pinfunction "2_2") (pintype "passive"))
      (node (ref "C47") (pin "1") (pinfunction "1_1") (pintype "passive"))
      (node (ref "L2") (pin "1") (pinfunction "P$1_1") (pintype "passive"))
    )
    (net (code "77") (name "Net-(L2-P$2)") (class "Default")
      (node (ref "C47") (pin "2") (pinfunction "2_2") (pintype "passive"))
      (node (ref "C50") (pin "2") (pinfunction "2_2") (pintype "passive"))
      (node (ref "L2") (pin "2") (pinfunction "P$2_2") (pintype "passive"))
      (node (ref "L4") (pin "1") (pinfunction "P$1_1") (pintype "passive"))
    )
    (net (code "78") (name "Net-(L4-P$2)") (class "Default")
      (node (ref "C56") (pin "2") (pinfunction "2_2") (pintype "passive"))
      (node (ref "C59") (pin "1") (pinfunction "1_1") (pintype "passive"))
      (node (ref "L4") (pin "2") (pinfunction "P$2_2") (pintype "passive"))
      (node (ref "L5") (pin "1") (pinfunction "P$1_1") (pintype "passive"))
    )
    (net (code "79") (name "Net-(L5-P$2)") (class "Default")
      (node (ref "C59") (pin "2") (pinfunction "2_2") (pintype "passive"))
      (node (ref "C91") (pin "1") (pinfunction "1_1") (pintype "passive"))
      (node (ref "L5") (pin "2") (pinfunction "P$2_2") (pintype "passive"))
    )
    (net (code "80") (name "Net-(L7-P$2)") (class "Default")
      (node (ref "C57") (pin "2") (pinfunction "2_2") (pintype "passive"))
      (node (ref "L7") (pin "2") (pinfunction "P$2_2") (pintype "passive"))
      (node (ref "L8") (pin "1") (pinfunction "P$1_1") (pintype "passive"))
    )
    (net (code "81") (name "Net-(L8-P$2)") (class "Default")
      (node (ref "C60") (pin "1") (pinfunction "1_1") (pintype "passive"))
      (node (ref "L8") (pin "2") (pinfunction "P$2_2") (pintype "passive"))
    )
    (net (code "82") (name "Net-(L12-P$1)") (class "Default")
      (node (ref "C90") (pin "1") (pinfunction "1_1") (pintype "passive"))
      (node (ref "IC15") (pin "RF_OUT") (pinfunction "RF_OUT_RF_OUT") (pintype "bidirectional"))
      (node (ref "L12") (pin "1") (pinfunction "P$1_1") (pintype "passive"))
    )
    (net (code "83") (name "Net-(L15-P$2)") (class "Default")
      (node (ref "C102") (pin "1") (pinfunction "1_1") (pintype "passive"))
      (node (ref "L15") (pin "2") (pinfunction "P$2_2") (pintype "passive"))
      (node (ref "L16") (pin "1") (pinfunction "P$1_1") (pintype "passive"))
    )
    (net (code "84") (name "Net-(L16-P$2)") (class "Default")
      (node (ref "C98") (pin "1") (pinfunction "1_1") (pintype "passive"))
      (node (ref "L16") (pin "2") (pinfunction "P$2_2") (pintype "passive"))
    )
    (net (code "85") (name "Net-(L17-P$1)") (class "Default")
      (node (ref "C101") (pin "1") (pinfunction "1_1") (pintype "passive"))
      (node (ref "L17") (pin "1") (pinfunction "P$1_1") (pintype "passive"))
    )
    (net (code "86") (name "Net-(L18-P$1)") (class "Default")
      (node (ref "C102") (pin "2") (pinfunction "2_2") (pintype "passive"))
      (node (ref "IC17") (pin "7") (pinfunction "OUT_7") (pintype "passive"))
      (node (ref "IC17") (pin "8") (pinfunction "OUT_8") (pintype "passive"))
      (node (ref "IC17") (pin "9") (pinfunction "OUT_9") (pintype "passive"))
      (node (ref "L18") (pin "1") (pinfunction "P$1_1") (pintype "passive"))
    )
    (net (code "87") (name "Net-(Q4-D)") (class "Default")
      (node (ref "Q4") (pin "3") (pinfunction "D_3") (pintype "passive"))
      (node (ref "Q5") (pin "1") (pinfunction "G_1") (pintype "passive"))
      (node (ref "R22") (pin "1") (pinfunction "P$1_1") (pintype "passive"))
    )
    (net (code "88") (name "Net-(R5-P$2)") (class "Default")
      (node (ref "LED2") (pin "A") (pinfunction "A_A") (pintype "passive"))
      (node (ref "R5") (pin "2") (pinfunction "P$2_2") (pintype "passive"))
    )
    (net (code "89") (name "Net-(R6-P$2)") (class "Default")
      (node (ref "LED1") (pin "A") (pinfunction "A_A") (pintype "passive"))
      (node (ref "R6") (pin "2") (pinfunction "P$2_2") (pintype "passive"))
    )
    (net (code "90") (name "Net-(R17-P$1)") (class "Default")
      (node (ref "JP7") (pin "4") (pinfunction "4_4") (pintype "passive"))
      (node (ref "R17") (pin "1") (pinfunction "P$1_1") (pintype "passive"))
    )
    (net (code "91") (name "Net-(R18-P$1)") (class "Default")
      (node (ref "JP7") (pin "3") (pinfunction "3_3") (pintype "passive"))
      (node (ref "R18") (pin "1") (pinfunction "P$1_1") (pintype "passive"))
    )
    (net (code "92") (name "Net-(R19-P$2)") (class "Default")
      (node (ref "LED4") (pin "A") (pinfunction "A_A") (pintype "passive"))
      (node (ref "R19") (pin "2") (pinfunction "P$2_2") (pintype "passive"))
    )
    (net (code "93") (name "Net-(R28-P$1)") (class "Default")
      (node (ref "LED5") (pin "A") (pinfunction "A_A") (pintype "passive"))
      (node (ref "R28") (pin "1") (pinfunction "P$1_1") (pintype "passive"))
    )
    (net (code "94") (name "Net-(R29-P$1)") (class "Default")
      (node (ref "LED6") (pin "A") (pinfunction "A_A") (pintype "passive"))
      (node (ref "R29") (pin "1") (pinfunction "P$1_1") (pintype "passive"))
    )
    (net (code "95") (name "Net-(R30-P$1)") (class "Default")
      (node (ref "LED7") (pin "A") (pinfunction "A_A") (pintype "passive"))
      (node (ref "R30") (pin "1") (pinfunction "P$1_1") (pintype "passive"))
    )
    (net (code "96") (name "Net-(R31-P$1)") (class "Default")
      (node (ref "LED8") (pin "A") (pinfunction "A_A") (pintype "passive"))
      (node (ref "R31") (pin "1") (pinfunction "P$1_1") (pintype "passive"))
    )
    (net (code "97") (name "Net-(X3-OUT)") (class "Default")
      (node (ref "C22") (pin "1") (pinfunction "1_1") (pintype "passive"))
      (node (ref "X3") (pin "4") (pinfunction "OUT_4") (pintype "output"))
    )
    (net (code "98") (name "Net-(X4-OUT)") (class "Default")
      (node (ref "C24") (pin "1") (pinfunction "1_1") (pintype "passive"))
      (node (ref "X4") (pin "4") (pinfunction "OUT_4") (pintype "output"))
    )
    (net (code "99") (name "PA_POWER") (class "Default")
      (node (ref "C61") (pin "1") (pinfunction "1_1") (pintype "passive"))
      (node (ref "IC17") (pin "6") (pinfunction "PDET_6") (pintype "output"))
      (node (ref "IC9") (pin "61") (pinfunction "PD0_61") (pintype "bidirectional"))
      (node (ref "TP16") (pin "TP") (pinfunction "TP_TP") (pintype "input"))
    )
    (net (code "100") (name "PA_PWR") (class "Default")
      (node (ref "C103") (pin "1") (pinfunction "1_1") (pintype "passive"))
      (node (ref "C104") (pin "1") (pinfunction "1_1") (pintype "passive"))
      (node (ref "C106") (pin "1") (pinfunction "1_1") (pintype "passive"))
      (node (ref "C84") (pin "1") (pinfunction "1_1") (pintype "passive"))
      (node (ref "C85") (pin "1") (pinfunction "1_1") (pintype "passive"))
      (node (ref "C86") (pin "2") (pinfunction "2_2") (pintype "passive"))
      (node (ref "C94") (pin "1") (pinfunction "1_1") (pintype "passive"))
      (node (ref "C95") (pin "1") (pinfunction "1_1") (pintype "passive"))
      (node (ref "C96") (pin "1") (pinfunction "1_1") (pintype "passive"))
      (node (ref "C99") (pin "1") (pinfunction "1_1") (pintype "passive"))
      (node (ref "IC17") (pin "2") (pinfunction "VBIAS_2") (pintype "input"))
      (node (ref "JP10") (pin "2") (pinfunction "2_2") (pintype "passive"))
      (node (ref "L12") (pin "2") (pinfunction "P$2_2") (pintype "passive"))
      (node (ref "L14") (pin "2") (pinfunction "P$2_2") (pintype "passive"))
      (node (ref "L18") (pin "2") (pinfunction "P$2_2") (pintype "passive"))
      (node (ref "Q5") (pin "3") (pinfunction "D_3") (pintype "passive"))
      (node (ref "R16") (pin "1") (pinfunction "P$1_1") (pintype "passive"))
      (node (ref "R19") (pin "1") (pinfunction "P$1_1") (pintype "passive"))
      (node (ref "R26") (pin "1") (pinfunction "P$1_1") (pintype "passive"))
      (node (ref "R27") (pin "1") (pinfunction "P$1_1") (pintype "passive"))
    )
    (net (code "101") (name "PWR{slash}INT") (class "Default")
      (node (ref "IC9") (pin "10") (pinfunction "PD7_10") (pintype "bidirectional"))
      (node (ref "SV3") (pin "47") (pinfunction "47_47") (pintype "passive"))
    )
    (net (code "102") (name "PWR{slash}RXD") (class "Default")
      (node (ref "IC9") (pin "8") (pinfunction "PE1_8") (pintype "bidirectional"))
      (node (ref "SV2") (pin "47") (pinfunction "47_47") (pintype "passive"))
    )
    (net (code "103") (name "PWR{slash}TXD") (class "Default")
      (node (ref "IC9") (pin "9") (pinfunction "PE0_9") (pintype "bidirectional"))
      (node (ref "SV2") (pin "48") (pinfunction "48_48") (pintype "passive"))
    )
    (net (code "104") (name "RX_CLK") (class "Default")
      (node (ref "IC5") (pin "7") (pinfunction "A6_7") (pintype "bidirectional"))
      (node (ref "IC8") (pin "8") (pinfunction "SCK_8") (pintype "bidirectional"))
      (node (ref "TP19") (pin "TP") (pinfunction "TP_TP") (pintype "input"))
    )
    (net (code "105") (name "RX_CS") (class "Default")
      (node (ref "IC5") (pin "8") (pinfunction "A7_8") (pintype "bidirectional"))
      (node (ref "IC8") (pin "11") (pinfunction "CSN_11") (pintype "bidirectional"))
      (node (ref "TP22") (pin "TP") (pinfunction "TP_TP") (pintype "input"))
    )
    (net (code "106") (name "RX_GPIO0") (class "Default")
      (node (ref "IC5") (pin "1") (pinfunction "A1_1") (pintype "bidirectional"))
      (node (ref "IC8") (pin "10") (pinfunction "GPIO0_10") (pintype "bidirectional"))
      (node (ref "TP21") (pin "TP") (pinfunction "TP_TP") (pintype "input"))
    )
    (net (code "107") (name "RX_GPIO2") (class "Default")
      (node (ref "IC8") (pin "4") (pinfunction "GPIO2_4") (pintype "bidirectional"))
    )
    (net (code "108") (name "RX_GPIO3") (class "Default")
      (node (ref "IC8") (pin "3") (pinfunction "GPIO3_3") (pintype "bidirectional"))
    )
    (net (code "109") (name "RX_MISO") (class "Default")
      (node (ref "IC5") (pin "6") (pinfunction "A5_6") (pintype "bidirectional"))
      (node (ref "IC8") (pin "9") (pinfunction "MISO_9") (pintype "bidirectional"))
      (node (ref "TP20") (pin "TP") (pinfunction "TP_TP") (pintype "input"))
    )
    (net (code "110") (name "RX_MOSI") (class "Default")
      (node (ref "IC5") (pin "5") (pinfunction "A4_5") (pintype "bidirectional"))
      (node (ref "IC8") (pin "7") (pinfunction "MOSI_7") (pintype "bidirectional"))
      (node (ref "TP18") (pin "TP") (pinfunction "TP_TP") (pintype "input"))
    )
    (net (code "111") (name "RX_REG_EN") (class "Default")
      (node (ref "IC1") (pin "3") (pinfunction "EN_3") (pintype "input"))
      (node (ref "IC9") (pin "23") (pinfunction "PA6_23") (pintype "bidirectional"))
      (node (ref "R2") (pin "1") (pinfunction "P$1_1") (pintype "passive"))
    )
    (net (code "112") (name "RX_RST") (class "Default")
      (node (ref "IC5") (pin "9") (pinfunction "A8_9") (pintype "bidirectional"))
      (node (ref "IC8") (pin "2") (pinfunction "NRESET_2") (pintype "bidirectional"))
      (node (ref "R10") (pin "1") (pinfunction "P$1_1") (pintype "passive"))
      (node (ref "TP17") (pin "TP") (pinfunction "TP_TP") (pintype "input"))
    )
    (net (code "113") (name "RX{slash}GPIO0") (class "Default")
      (node (ref "IC5") (pin "20") (pinfunction "B1_20") (pintype "bidirectional"))
      (node (ref "IC9") (pin "4") (pinfunction "PB7_4") (pintype "bidirectional"))
    )
    (net (code "114") (name "SWCLK") (class "Default")
      (node (ref "IC9") (pin "52") (pinfunction "PC0/TCK/SWCLK_52") (pintype "bidirectional"))
      (node (ref "J3") (pin "4") (pinfunction "SWCLK_4") (pintype "bidirectional"))
      (node (ref "SV2") (pin "3") (pinfunction "3_3") (pintype "passive"))
    )
    (net (code "115") (name "SWDIO") (class "Default")
      (node (ref "IC9") (pin "51") (pinfunction "PC1/TMS/SWDIO_51") (pintype "bidirectional"))
      (node (ref "J3") (pin "2") (pinfunction "SWDAT_2") (pintype "bidirectional"))
      (node (ref "SV2") (pin "4") (pinfunction "4_4") (pintype "passive"))
    )
    (net (code "116") (name "SWO") (class "Default")
      (node (ref "IC9") (pin "49") (pinfunction "PC3/TDO/SWO_49") (pintype "bidirectional"))
      (node (ref "J3") (pin "6") (pinfunction "SWO_6") (pintype "bidirectional"))
      (node (ref "SV3") (pin "3") (pinfunction "3_3") (pintype "passive"))
    )
    (net (code "117") (name "TC{slash}RX{slash}CS") (class "Default")
      (node (ref "IC5") (pin "13") (pinfunction "B7_13") (pintype "bidirectional"))
      (node (ref "IC9") (pin "20") (pinfunction "PA3/SSI0FSS_20") (pintype "bidirectional"))
    )
    (net (code "118") (name "TC{slash}TXRX{slash}CLK") (class "Default")
      (node (ref "IC10") (pin "6") (pinfunction "SCK_6") (pintype "input"))
      (node (ref "IC5") (pin "14") (pinfunction "B6_14") (pintype "bidirectional"))
      (node (ref "IC6") (pin "14") (pinfunction "B6_14") (pintype "bidirectional"))
      (node (ref "IC9") (pin "30") (pinfunction "PF2_30") (pintype "bidirectional"))
    )
    (net (code "119") (name "TC{slash}TXRX{slash}MISO") (class "Default")
      (node (ref "IC10") (pin "2") (pinfunction "SO_2") (pintype "output"))
      (node (ref "IC5") (pin "15") (pinfunction "B5_15") (pintype "bidirectional"))
      (node (ref "IC6") (pin "15") (pinfunction "B5_15") (pintype "bidirectional"))
      (node (ref "IC9") (pin "28") (pinfunction "PF0_28") (pintype "bidirectional"))
    )
    (net (code "120") (name "TC{slash}TXRX{slash}MOSI") (class "Default")
      (node (ref "IC10") (pin "5") (pinfunction "SI_5") (pintype "input"))
      (node (ref "IC5") (pin "16") (pinfunction "B4_16") (pintype "bidirectional"))
      (node (ref "IC6") (pin "16") (pinfunction "B4_16") (pintype "bidirectional"))
      (node (ref "IC9") (pin "29") (pinfunction "PF1_29") (pintype "bidirectional"))
    )
    (net (code "121") (name "TC{slash}TXRX{slash}RST") (class "Default")
      (node (ref "IC5") (pin "12") (pinfunction "B8_12") (pintype "bidirectional"))
      (node (ref "IC6") (pin "17") (pinfunction "B3_17") (pintype "bidirectional"))
      (node (ref "IC9") (pin "1") (pinfunction "PB6_1") (pintype "bidirectional"))
    )
    (net (code "122") (name "TC{slash}TX{slash}CS") (class "Default")
      (node (ref "IC6") (pin "13") (pinfunction "B7_13") (pintype "bidirectional"))
      (node (ref "IC9") (pin "31") (pinfunction "PF3_31") (pintype "bidirectional"))
    )
    (net (code "123") (name "TMP{slash}SCL") (class "Default")
      (node (ref "IC14") (pin "1") (pinfunction "SCL_1") (pintype "passive"))
      (node (ref "IC16") (pin "2") (pinfunction "SCL_2") (pintype "input"))
      (node (ref "IC18") (pin "2") (pinfunction "SCL_2") (pintype "input"))
      (node (ref "IC9") (pin "47") (pinfunction "PB2/I2C0SCL_47") (pintype "bidirectional"))
      (node (ref "R24") (pin "1") (pinfunction "P$1_1") (pintype "passive"))
      (node (ref "TP10") (pin "TP") (pinfunction "TP_TP") (pintype "input"))
    )
    (net (code "124") (name "TMP{slash}SDA") (class "Default")
      (node (ref "IC14") (pin "6") (pinfunction "SDA_6") (pintype "passive"))
      (node (ref "IC16") (pin "1") (pinfunction "SDA_1") (pintype "open_collector"))
      (node (ref "IC18") (pin "1") (pinfunction "SDA_1") (pintype "open_collector"))
      (node (ref "IC9") (pin "48") (pinfunction "PB3/I2C0SDA_48") (pintype "bidirectional"))
      (node (ref "R23") (pin "1") (pinfunction "P$1_1") (pintype "passive"))
      (node (ref "TP9") (pin "TP") (pinfunction "TP_TP") (pintype "input"))
    )
    (net (code "125") (name "TX_CLK") (class "Default")
      (node (ref "IC6") (pin "7") (pinfunction "A6_7") (pintype "bidirectional"))
      (node (ref "IC7") (pin "8") (pinfunction "SCK_8") (pintype "bidirectional"))
      (node (ref "TP8") (pin "TP") (pinfunction "TP_TP") (pintype "input"))
    )
    (net (code "126") (name "TX_CS") (class "Default")
      (node (ref "IC3") (pin "1") (pinfunction "P1.1_1") (pintype "bidirectional"))
      (node (ref "IC6") (pin "8") (pinfunction "A7_8") (pintype "bidirectional"))
      (node (ref "IC7") (pin "11") (pinfunction "CSN_11") (pintype "bidirectional"))
      (node (ref "TP7") (pin "TP") (pinfunction "TP_TP") (pintype "input"))
    )
    (net (code "127") (name "TX_GPIO0") (class "Default")
      (node (ref "IC3") (pin "15") (pinfunction "P1.3_15") (pintype "bidirectional"))
      (node (ref "IC6") (pin "1") (pinfunction "A1_1") (pintype "bidirectional"))
      (node (ref "IC7") (pin "10") (pinfunction "GPIO0_10") (pintype "bidirectional"))
      (node (ref "TP13") (pin "TP") (pinfunction "TP_TP") (pintype "input"))
    )
    (net (code "128") (name "TX_GPIO2") (class "Default")
      (node (ref "IC7") (pin "4") (pinfunction "GPIO2_4") (pintype "bidirectional"))
    )
    (net (code "129") (name "TX_GPIO3") (class "Default")
      (node (ref "IC7") (pin "3") (pinfunction "GPIO3_3") (pintype "bidirectional"))
      (node (ref "IC77") (pin "1") (pinfunction "A_1") (pintype "input"))
      (node (ref "R29") (pin "2") (pinfunction "P$2_2") (pintype "passive"))
      (node (ref "TP15") (pin "TP") (pinfunction "TP_TP") (pintype "input"))
    )
    (net (code "130") (name "TX_MISO") (class "Default")
      (node (ref "IC6") (pin "6") (pinfunction "A5_6") (pintype "bidirectional"))
      (node (ref "IC7") (pin "9") (pinfunction "MISO_9") (pintype "bidirectional"))
      (node (ref "TP12") (pin "TP") (pinfunction "TP_TP") (pintype "input"))
    )
    (net (code "131") (name "TX_MOSI") (class "Default")
      (node (ref "IC6") (pin "5") (pinfunction "A4_5") (pintype "bidirectional"))
      (node (ref "IC7") (pin "7") (pinfunction "MOSI_7") (pintype "bidirectional"))
      (node (ref "TP11") (pin "TP") (pinfunction "TP_TP") (pintype "input"))
    )
    (net (code "132") (name "TX_REG_EN") (class "Default")
      (node (ref "IC2") (pin "3") (pinfunction "EN_3") (pintype "input"))
      (node (ref "IC9") (pin "24") (pinfunction "PA7_24") (pintype "bidirectional"))
      (node (ref "R4") (pin "1") (pinfunction "P$1_1") (pintype "passive"))
    )
    (net (code "133") (name "TX_RST") (class "Default")
      (node (ref "IC3") (pin "16") (pinfunction "P1.2_16") (pintype "bidirectional"))
      (node (ref "IC6") (pin "4") (pinfunction "A3_4") (pintype "bidirectional"))
      (node (ref "IC7") (pin "2") (pinfunction "NRESET_2") (pintype "bidirectional"))
      (node (ref "R7") (pin "1") (pinfunction "P$1_1") (pintype "passive"))
      (node (ref "TP6") (pin "TP") (pinfunction "TP_TP") (pintype "input"))
    )
    (net (code "134") (name "TX{slash}GPIO0") (class "Default")
      (node (ref "IC6") (pin "20") (pinfunction "B1_20") (pintype "bidirectional"))
      (node (ref "IC9") (pin "19") (pinfunction "PA2/SSI0CLK_19") (pintype "bidirectional"))
    )
    (net (code "135") (name "TX{slash}WDT{slash}ACK") (class "Default")
      (node (ref "IC6") (pin "18") (pinfunction "B2_18") (pintype "bidirectional"))
      (node (ref "IC9") (pin "21") (pinfunction "PA4/SSI0RX_21") (pintype "bidirectional"))
    )
    (net (code "136") (name "TX{slash}WDT{slash}ERR") (class "Default")
      (node (ref "IC6") (pin "12") (pinfunction "B8_12") (pintype "bidirectional"))
      (node (ref "IC9") (pin "22") (pinfunction "PA5/SSI0TX_22") (pintype "bidirectional"))
    )
    (net (code "137") (name "WDT_ACK") (class "Default")
      (node (ref "IC3") (pin "13") (pinfunction "P1.5_13") (pintype "bidirectional"))
      (node (ref "IC6") (pin "3") (pinfunction "A2_3") (pintype "bidirectional"))
    )
    (net (code "138") (name "WDT_ERR") (class "Default")
      (node (ref "IC3") (pin "14") (pinfunction "P1.4_14") (pintype "bidirectional"))
      (node (ref "IC6") (pin "9") (pinfunction "A8_9") (pintype "bidirectional"))
    )
    (net (code "139") (name "WDT_PA_EN") (class "Default")
      (node (ref "IC3") (pin "2") (pinfunction "P1.0_2") (pintype "bidirectional"))
      (node (ref "IC77") (pin "2") (pinfunction "B_2") (pintype "input"))
      (node (ref "R28") (pin "2") (pinfunction "P$2_2") (pintype "passive"))
      (node (ref "TP14") (pin "TP") (pinfunction "TP_TP") (pintype "input"))
    )
    (net (code "140") (name "WDT{slash}KICK") (class "Default")
      (node (ref "IC13") (pin "1") (pinfunction "WDI_1") (pintype "input"))
      (node (ref "IC9") (pin "5") (pinfunction "PF4_5") (pintype "bidirectional"))
    )
    (net (code "141") (name "unconnected-(IC3-P2.6-Pad8)") (class "Default")
      (node (ref "IC3") (pin "8") (pinfunction "P2.6_8") (pintype "bidirectional"))
    )
    (net (code "142") (name "unconnected-(IC3-P2.7-Pad7)") (class "Default")
      (node (ref "IC3") (pin "7") (pinfunction "P2.7_7") (pintype "bidirectional"))
    )
    (net (code "143") (name "unconnected-(IC3-TRI0--Pad12)") (class "Default")
      (node (ref "IC3") (pin "12") (pinfunction "TRI0-_12") (pintype "bidirectional"))
    )
    (net (code "144") (name "unconnected-(IC5-A2-Pad3)") (class "Default")
      (node (ref "IC5") (pin "3") (pinfunction "A2_3") (pintype "bidirectional"))
    )
    (net (code "145") (name "unconnected-(IC5-A3-Pad4)") (class "Default")
      (node (ref "IC5") (pin "4") (pinfunction "A3_4") (pintype "bidirectional"))
    )
    (net (code "146") (name "unconnected-(IC5-B2-Pad18)") (class "Default")
      (node (ref "IC5") (pin "18") (pinfunction "B2_18") (pintype "bidirectional"))
    )
    (net (code "147") (name "unconnected-(IC5-B3-Pad17)") (class "Default")
      (node (ref "IC5") (pin "17") (pinfunction "B3_17") (pintype "bidirectional"))
    )
    (net (code "148") (name "unconnected-(IC7-NC-Pad16)") (class "Default")
      (node (ref "IC7") (pin "16") (pinfunction "NC_16") (pintype "bidirectional"))
    )
    (net (code "149") (name "unconnected-(IC7-XOSC_Q2-Pad31)") (class "Default")
      (node (ref "IC7") (pin "31") (pinfunction "XOSC_Q2_31") (pintype "bidirectional"))
    )
    (net (code "150") (name "unconnected-(IC8-NC-Pad16)") (class "Default")
      (node (ref "IC8") (pin "16") (pinfunction "NC_16") (pintype "bidirectional"))
    )
    (net (code "151") (name "unconnected-(IC8-PA-Pad17)") (class "Default")
      (node (ref "IC8") (pin "17") (pinfunction "PA_17") (pintype "bidirectional"))
    )
    (net (code "152") (name "unconnected-(IC8-TRX_SW-Pad18)") (class "Default")
      (node (ref "IC8") (pin "18") (pinfunction "TRX_SW_18") (pintype "bidirectional"))
    )
    (net (code "153") (name "unconnected-(IC8-XOSC_Q2-Pad31)") (class "Default")
      (node (ref "IC8") (pin "31") (pinfunction "XOSC_Q2_31") (pintype "bidirectional"))
    )
    (net (code "154") (name "unconnected-(IC9-PD1-Pad62)") (class "Default")
      (node (ref "IC9") (pin "62") (pinfunction "PD1_62") (pintype "bidirectional"))
    )
    (net (code "155") (name "unconnected-(IC9-PD2-Pad63)") (class "Default")
      (node (ref "IC9") (pin "63") (pinfunction "PD2_63") (pintype "bidirectional"))
    )
    (net (code "156") (name "unconnected-(IC9-PD3-Pad64)") (class "Default")
      (node (ref "IC9") (pin "64") (pinfunction "PD3_64") (pintype "bidirectional"))
    )
    (net (code "157") (name "unconnected-(IC9-~{HIB}-Pad33)") (class "Default")
      (node (ref "IC9") (pin "33") (pinfunction "~{HIB}_33") (pintype "bidirectional"))
    )
    (net (code "158") (name "unconnected-(IC11-AUX_CL-Pad7)") (class "Default")
      (node (ref "IC11") (pin "7") (pinfunction "AUX_CL_7") (pintype "bidirectional"))
    )
    (net (code "159") (name "unconnected-(IC11-AUX_DA-Pad21)") (class "Default")
      (node (ref "IC11") (pin "21") (pinfunction "AUX_DA_21") (pintype "bidirectional"))
    )
    (net (code "160") (name "unconnected-(IC11-INT-Pad12)") (class "Default")
      (node (ref "IC11") (pin "12") (pinfunction "INT_12") (pintype "bidirectional"))
    )
    (net (code "161") (name "unconnected-(IC12-B1-Pad20)") (class "Default")
      (node (ref "IC12") (pin "20") (pinfunction "B1_20") (pintype "bidirectional"))
    )
    (net (code "162") (name "unconnected-(IC12-B2-Pad18)") (class "Default")
      (node (ref "IC12") (pin "18") (pinfunction "B2_18") (pintype "bidirectional"))
    )
    (net (code "163") (name "unconnected-(IC12-B5-Pad15)") (class "Default")
      (node (ref "IC12") (pin "15") (pinfunction "B5_15") (pintype "bidirectional"))
    )
    (net (code "164") (name "unconnected-(IC12-B6-Pad14)") (class "Default")
      (node (ref "IC12") (pin "14") (pinfunction "B6_14") (pintype "bidirectional"))
    )
    (net (code "165") (name "unconnected-(IC12-B7-Pad13)") (class "Default")
      (node (ref "IC12") (pin "13") (pinfunction "B7_13") (pintype "bidirectional"))
    )
    (net (code "166") (name "unconnected-(IC12-B8-Pad12)") (class "Default")
      (node (ref "IC12") (pin "12") (pinfunction "B8_12") (pintype "bidirectional"))
    )
    (net (code "167") (name "unconnected-(IC16-OS-Pad3)") (class "Default")
      (node (ref "IC16") (pin "3") (pinfunction "OS_3") (pintype "open_collector"))
    )
    (net (code "168") (name "unconnected-(IC18-OS-Pad3)") (class "Default")
      (node (ref "IC18") (pin "3") (pinfunction "OS_3") (pintype "open_collector"))
    )
    (net (code "169") (name "unconnected-(J3-KEY-Pad7)") (class "Default")
      (node (ref "J3") (pin "7") (pinfunction "KEY_7") (pintype "bidirectional"))
    )
    (net (code "170") (name "unconnected-(J3-NC-Pad8)") (class "Default")
      (node (ref "J3") (pin "8") (pinfunction "NC_8") (pintype "no_connect"))
    )
    (net (code "171") (name "unconnected-(SV2-Pad5)") (class "Default")
      (node (ref "SV2") (pin "5") (pinfunction "5_5") (pintype "passive"))
    )
    (net (code "172") (name "unconnected-(SV2-Pad6)") (class "Default")
      (node (ref "SV2") (pin "6") (pinfunction "6_6") (pintype "passive"))
    )
    (net (code "173") (name "unconnected-(SV2-Pad7)") (class "Default")
      (node (ref "SV2") (pin "7") (pinfunction "7_7") (pintype "passive"))
    )
    (net (code "174") (name "unconnected-(SV2-Pad8)") (class "Default")
      (node (ref "SV2") (pin "8") (pinfunction "8_8") (pintype "passive"))
    )
    (net (code "175") (name "unconnected-(SV2-Pad9)") (class "Default")
      (node (ref "SV2") (pin "9") (pinfunction "9_9") (pintype "passive"))
    )
    (net (code "176") (name "unconnected-(SV2-Pad11)") (class "Default")
      (node (ref "SV2") (pin "11") (pinfunction "11_11") (pintype "passive"))
    )
    (net (code "177") (name "unconnected-(SV2-Pad12)") (class "Default")
      (node (ref "SV2") (pin "12") (pinfunction "12_12") (pintype "passive"))
    )
    (net (code "178") (name "unconnected-(SV2-Pad13)") (class "Default")
      (node (ref "SV2") (pin "13") (pinfunction "13_13") (pintype "passive"))
    )
    (net (code "179") (name "unconnected-(SV2-Pad14)") (class "Default")
      (node (ref "SV2") (pin "14") (pinfunction "14_14") (pintype "passive"))
    )
    (net (code "180") (name "unconnected-(SV2-Pad17)") (class "Default")
      (node (ref "SV2") (pin "17") (pinfunction "17_17") (pintype "passive"))
    )
    (net (code "181") (name "unconnected-(SV2-Pad18)") (class "Default")
      (node (ref "SV2") (pin "18") (pinfunction "18_18") (pintype "passive"))
    )
    (net (code "182") (name "unconnected-(SV2-Pad19)") (class "Default")
      (node (ref "SV2") (pin "19") (pinfunction "19_19") (pintype "passive"))
    )
    (net (code "183") (name "unconnected-(SV2-Pad20)") (class "Default")
      (node (ref "SV2") (pin "20") (pinfunction "20_20") (pintype "passive"))
    )
    (net (code "184") (name "unconnected-(SV2-Pad21)") (class "Default")
      (node (ref "SV2") (pin "21") (pinfunction "21_21") (pintype "passive"))
    )
    (net (code "185") (name "unconnected-(SV2-Pad23)") (class "Default")
      (node (ref "SV2") (pin "23") (pinfunction "23_23") (pintype "passive"))
    )
    (net (code "186") (name "unconnected-(SV2-Pad24)") (class "Default")
      (node (ref "SV2") (pin "24") (pinfunction "24_24") (pintype "passive"))
    )
    (net (code "187") (name "unconnected-(SV2-Pad25)") (class "Default")
      (node (ref "SV2") (pin "25") (pinfunction "25_25") (pintype "passive"))
    )
    (net (code "188") (name "unconnected-(SV2-Pad26)") (class "Default")
      (node (ref "SV2") (pin "26") (pinfunction "26_26") (pintype "passive"))
    )
    (net (code "189") (name "unconnected-(SV2-Pad27)") (class "Default")
      (node (ref "SV2") (pin "27") (pinfunction "27_27") (pintype "passive"))
    )
    (net (code "190") (name "unconnected-(SV2-Pad28)") (class "Default")
      (node (ref "SV2") (pin "28") (pinfunction "28_28") (pintype "passive"))
    )
    (net (code "191") (name "unconnected-(SV2-Pad29)") (class "Default")
      (node (ref "SV2") (pin "29") (pinfunction "29_29") (pintype "passive"))
    )
    (net (code "192") (name "unconnected-(SV2-Pad30)") (class "Default")
      (node (ref "SV2") (pin "30") (pinfunction "30_30") (pintype "passive"))
    )
    (net (code "193") (name "unconnected-(SV2-Pad31)") (class "Default")
      (node (ref "SV2") (pin "31") (pinfunction "31_31") (pintype "passive"))
    )
    (net (code "194") (name "unconnected-(SV2-Pad32)") (class "Default")
      (node (ref "SV2") (pin "32") (pinfunction "32_32") (pintype "passive"))
    )
    (net (code "195") (name "unconnected-(SV2-Pad33)") (class "Default")
      (node (ref "SV2") (pin "33") (pinfunction "33_33") (pintype "passive"))
    )
    (net (code "196") (name "unconnected-(SV2-Pad34)") (class "Default")
      (node (ref "SV2") (pin "34") (pinfunction "34_34") (pintype "passive"))
    )
    (net (code "197") (name "unconnected-(SV2-Pad35)") (class "Default")
      (node (ref "SV2") (pin "35") (pinfunction "35_35") (pintype "passive"))
    )
    (net (code "198") (name "unconnected-(SV2-Pad36)") (class "Default")
      (node (ref "SV2") (pin "36") (pinfunction "36_36") (pintype "passive"))
    )
    (net (code "199") (name "unconnected-(SV2-Pad37)") (class "Default")
      (node (ref "SV2") (pin "37") (pinfunction "37_37") (pintype "passive"))
    )
    (net (code "200") (name "unconnected-(SV2-Pad38)") (class "Default")
      (node (ref "SV2") (pin "38") (pinfunction "38_38") (pintype "passive"))
    )
    (net (code "201") (name "unconnected-(SV2-Pad39)") (class "Default")
      (node (ref "SV2") (pin "39") (pinfunction "39_39") (pintype "passive"))
    )
    (net (code "202") (name "unconnected-(SV2-Pad40)") (class "Default")
      (node (ref "SV2") (pin "40") (pinfunction "40_40") (pintype "passive"))
    )
    (net (code "203") (name "unconnected-(SV2-Pad41)") (class "Default")
      (node (ref "SV2") (pin "41") (pinfunction "41_41") (pintype "passive"))
    )
    (net (code "204") (name "unconnected-(SV2-Pad42)") (class "Default")
      (node (ref "SV2") (pin "42") (pinfunction "42_42") (pintype "passive"))
    )
    (net (code "205") (name "unconnected-(SV2-Pad43)") (class "Default")
      (node (ref "SV2") (pin "43") (pinfunction "43_43") (pintype "passive"))
    )
    (net (code "206") (name "unconnected-(SV2-Pad44)") (class "Default")
      (node (ref "SV2") (pin "44") (pinfunction "44_44") (pintype "passive"))
    )
    (net (code "207") (name "unconnected-(SV2-Pad45)") (class "Default")
      (node (ref "SV2") (pin "45") (pinfunction "45_45") (pintype "passive"))
    )
    (net (code "208") (name "unconnected-(SV2-Pad46)") (class "Default")
      (node (ref "SV2") (pin "46") (pinfunction "46_46") (pintype "passive"))
    )
    (net (code "209") (name "unconnected-(SV3-Pad6)") (class "Default")
      (node (ref "SV3") (pin "6") (pinfunction "6_6") (pintype "passive"))
    )
    (net (code "210") (name "unconnected-(SV3-Pad7)") (class "Default")
      (node (ref "SV3") (pin "7") (pinfunction "7_7") (pintype "passive"))
    )
    (net (code "211") (name "unconnected-(SV3-Pad8)") (class "Default")
      (node (ref "SV3") (pin "8") (pinfunction "8_8") (pintype "passive"))
    )
    (net (code "212") (name "unconnected-(SV3-Pad9)") (class "Default")
      (node (ref "SV3") (pin "9") (pinfunction "9_9") (pintype "passive"))
    )
    (net (code "213") (name "unconnected-(SV3-Pad10)") (class "Default")
      (node (ref "SV3") (pin "10") (pinfunction "10_10") (pintype "passive"))
    )
    (net (code "214") (name "unconnected-(SV3-Pad11)") (class "Default")
      (node (ref "SV3") (pin "11") (pinfunction "11_11") (pintype "passive"))
    )
    (net (code "215") (name "unconnected-(SV3-Pad12)") (class "Default")
      (node (ref "SV3") (pin "12") (pinfunction "12_12") (pintype "passive"))
    )
    (net (code "216") (name "unconnected-(SV3-Pad13)") (class "Default")
      (node (ref "SV3") (pin "13") (pinfunction "13_13") (pintype "passive"))
    )
    (net (code "217") (name "unconnected-(SV3-Pad14)") (class "Default")
      (node (ref "SV3") (pin "14") (pinfunction "14_14") (pintype "passive"))
    )
    (net (code "218") (name "unconnected-(SV3-Pad15)") (class "Default")
      (node (ref "SV3") (pin "15") (pinfunction "15_15") (pintype "passive"))
    )
    (net (code "219") (name "unconnected-(SV3-Pad16)") (class "Default")
      (node (ref "SV3") (pin "16") (pinfunction "16_16") (pintype "passive"))
    )
    (net (code "220") (name "unconnected-(SV3-Pad17)") (class "Default")
      (node (ref "SV3") (pin "17") (pinfunction "17_17") (pintype "passive"))
    )
    (net (code "221") (name "unconnected-(SV3-Pad18)") (class "Default")
      (node (ref "SV3") (pin "18") (pinfunction "18_18") (pintype "passive"))
    )
    (net (code "222") (name "unconnected-(SV3-Pad20)") (class "Default")
      (node (ref "SV3") (pin "20") (pinfunction "20_20") (pintype "passive"))
    )
    (net (code "223") (name "unconnected-(SV3-Pad22)") (class "Default")
      (node (ref "SV3") (pin "22") (pinfunction "22_22") (pintype "passive"))
    )
    (net (code "224") (name "unconnected-(SV3-Pad23)") (class "Default")
      (node (ref "SV3") (pin "23") (pinfunction "23_23") (pintype "passive"))
    )
    (net (code "225") (name "unconnected-(SV3-Pad24)") (class "Default")
      (node (ref "SV3") (pin "24") (pinfunction "24_24") (pintype "passive"))
    )
    (net (code "226") (name "unconnected-(SV3-Pad33)") (class "Default")
      (node (ref "SV3") (pin "33") (pinfunction "33_33") (pintype "passive"))
    )
    (net (code "227") (name "unconnected-(SV3-Pad34)") (class "Default")
      (node (ref "SV3") (pin "34") (pinfunction "34_34") (pintype "passive"))
    )
    (net (code "228") (name "unconnected-(SV3-Pad35)") (class "Default")
      (node (ref "SV3") (pin "35") (pinfunction "35_35") (pintype "passive"))
    )
    (net (code "229") (name "unconnected-(SV3-Pad36)") (class "Default")
      (node (ref "SV3") (pin "36") (pinfunction "36_36") (pintype "passive"))
    )
    (net (code "230") (name "unconnected-(SV3-Pad37)") (class "Default")
      (node (ref "SV3") (pin "37") (pinfunction "37_37") (pintype "passive"))
    )
    (net (code "231") (name "unconnected-(SV3-Pad38)") (class "Default")
      (node (ref "SV3") (pin "38") (pinfunction "38_38") (pintype "passive"))
    )
    (net (code "232") (name "unconnected-(SV3-Pad39)") (class "Default")
      (node (ref "SV3") (pin "39") (pinfunction "39_39") (pintype "passive"))
    )
    (net (code "233") (name "unconnected-(SV3-Pad40)") (class "Default")
      (node (ref "SV3") (pin "40") (pinfunction "40_40") (pintype "passive"))
    )
    (net (code "234") (name "unconnected-(SV3-Pad41)") (class "Default")
      (node (ref "SV3") (pin "41") (pinfunction "41_41") (pintype "passive"))
    )
    (net (code "235") (name "unconnected-(SV3-Pad42)") (class "Default")
      (node (ref "SV3") (pin "42") (pinfunction "42_42") (pintype "passive"))
    )
    (net (code "236") (name "unconnected-(SV3-Pad43)") (class "Default")
      (node (ref "SV3") (pin "43") (pinfunction "43_43") (pintype "passive"))
    )
    (net (code "237") (name "unconnected-(SV3-Pad44)") (class "Default")
      (node (ref "SV3") (pin "44") (pinfunction "44_44") (pintype "passive"))
    )
    (net (code "238") (name "unconnected-(SV3-Pad45)") (class "Default")
      (node (ref "SV3") (pin "45") (pinfunction "45_45") (pintype "passive"))
    )
    (net (code "239") (name "unconnected-(SV3-Pad46)") (class "Default")
      (node (ref "SV3") (pin "46") (pinfunction "46_46") (pintype "passive"))
    )
    (net (code "240") (name "unconnected-(SV3-Pad48)") (class "Default")
      (node (ref "SV3") (pin "48") (pinfunction "48_48") (pintype "passive"))
    )
    (net (code "241") (name "unconnected-(SV3-Pad49)") (class "Default")
      (node (ref "SV3") (pin "49") (pinfunction "49_49") (pintype "passive"))
    )
    (net (code "242") (name "unconnected-(SV3-Pad50)") (class "Default")
      (node (ref "SV3") (pin "50") (pinfunction "50_50") (pintype "passive"))
    )
    (net (code "243") (name "unconnected-(SV3-Pad51)") (class "Default")
      (node (ref "SV3") (pin "51") (pinfunction "51_51") (pintype "passive"))
    )
    (net (code "244") (name "unconnected-(SV3-Pad52)") (class "Default")
      (node (ref "SV3") (pin "52") (pinfunction "52_52") (pintype "passive"))
    )
    (net (code "245") (name "~{RST}") (class "Default")
      (node (ref "IC13") (pin "6") (pinfunction "*RESET_6") (pintype "output"))
      (node (ref "IC9") (pin "38") (pinfunction "~{RST}_38") (pintype "bidirectional"))
      (node (ref "J3") (pin "10") (pinfunction "NRST_10") (pintype "bidirectional"))
      (node (ref "R15") (pin "1") (pinfunction "P$1_1") (pintype "passive"))
      (node (ref "SV3") (pin "4") (pinfunction "4_4") (pintype "passive"))
    )
  )
)
